# design.net
KiCad netlist of a schematic drawn in Altium Designer
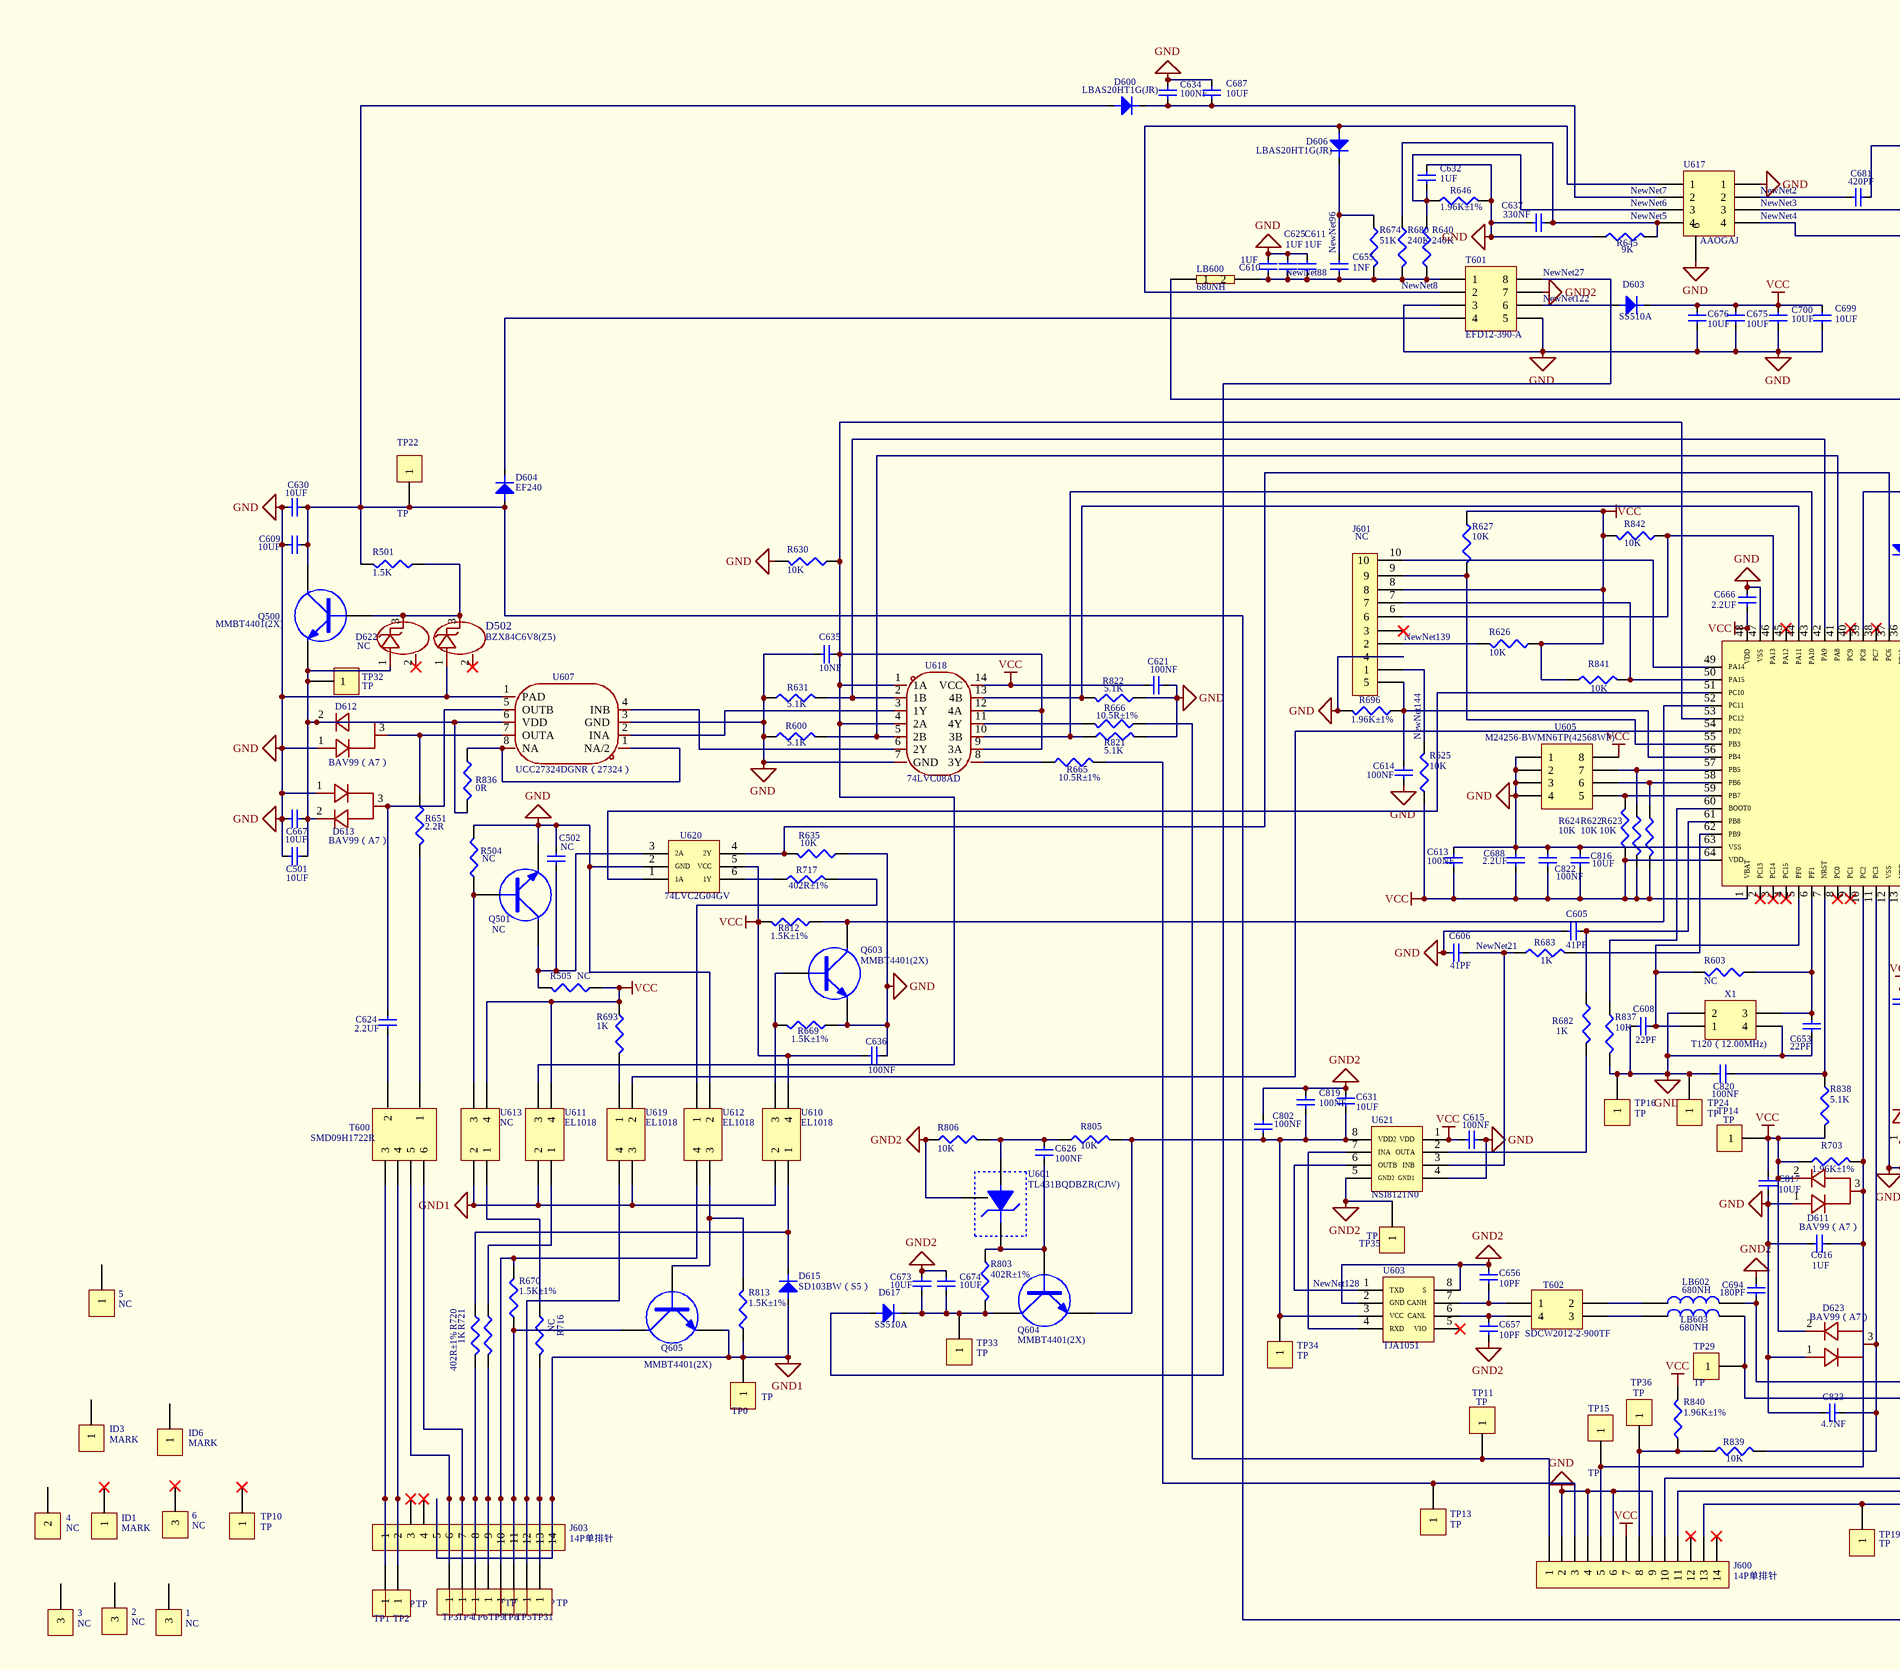
[diagram p0: 小板原理图.SchDoc, left]
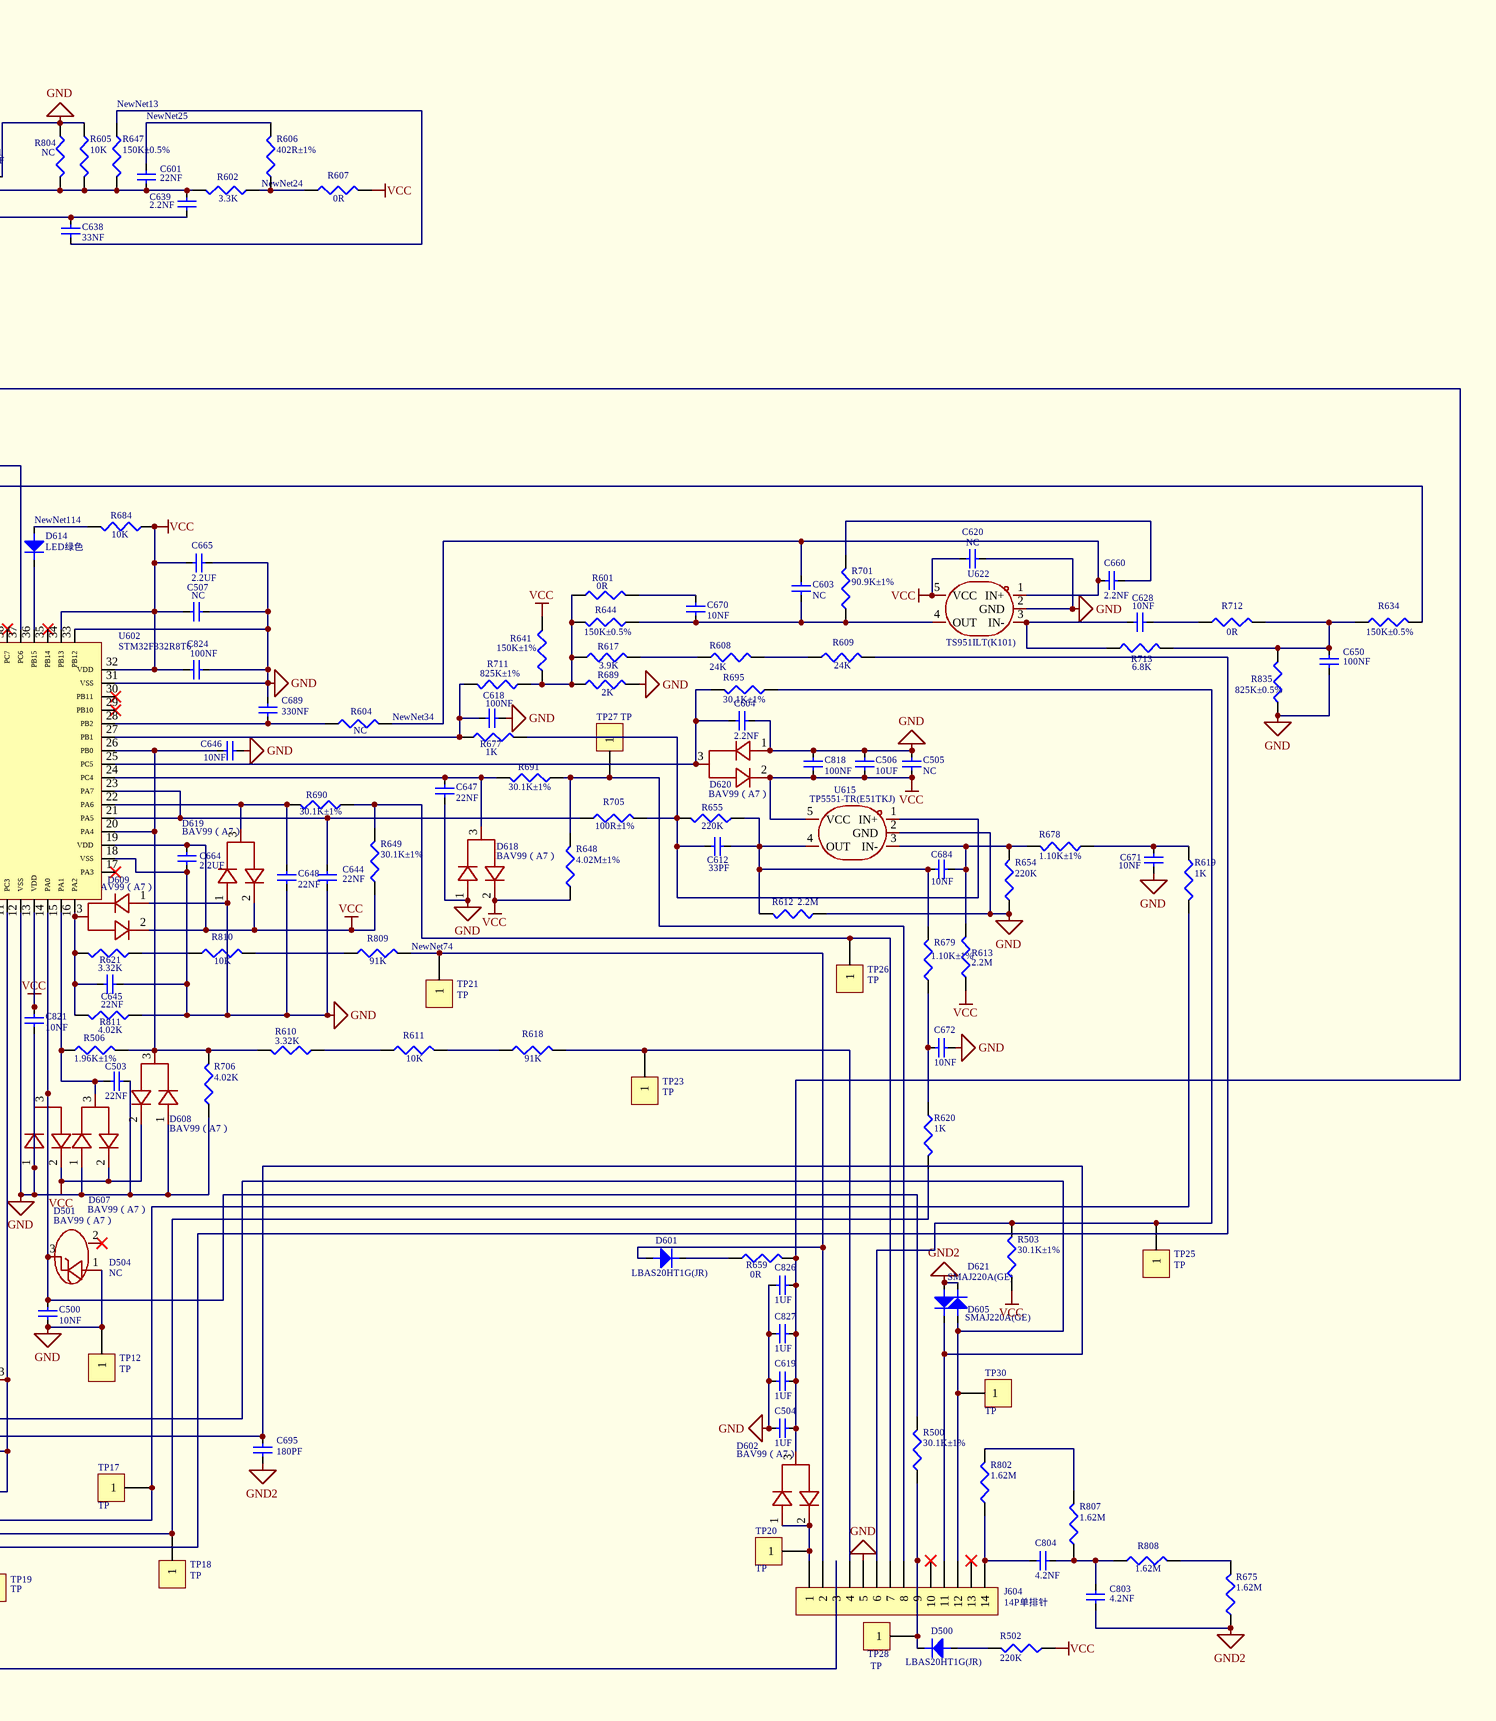
[diagram p1: 小板原理图.SchDoc, right]

(export (version "E")
  (design (tool "Eeschema 10.0.6"))
  (components
    (comp (ref "1") (value "NC") (footprint "27") (libsource (lib "*") (part "NC_")))
    (comp (ref "2") (value "NC") (footprint "28") (libsource (lib "*") (part "NC_")))
    (comp (ref "3") (value "NC") (footprint "29") (libsource (lib "*") (part "NC_")))
    (comp (ref "4") (value "NC") (footprint "30") (libsource (lib "") (part "NC__5")))
    (comp (ref "5") (value "NC") (footprint "30") (libsource (lib "") (part "NC__7")))
    (comp (ref "6") (value "NC") (footprint "30") (libsource (lib "*") (part "NC_")))
    (comp (ref "C500")
      (value "10NF")
      (footprint "33")
      (description "Capacitor")
      (libsource (lib "*") (part "CAP"))
    )
    (comp (ref "C501")
      (value "10UF")
      (footprint "4")
      (description "Capacitor")
      (libsource (lib "*") (part "CAP"))
    )
    (comp (ref "C502")
      (value "NC")
      (footprint "33")
      (description "Capacitor")
      (libsource (lib "*") (part "CAP"))
    )
    (comp (ref "C503")
      (value "22NF")
      (footprint "33")
      (description "Capacitor")
      (libsource (lib "*") (part "CAP"))
    )
    (comp (ref "C504")
      (value "1UF")
      (footprint "3")
      (description "Capacitor")
      (libsource (lib "*") (part "CAP"))
    )
    (comp (ref "C505")
      (value "NC")
      (footprint "3")
      (description "Capacitor")
      (libsource (lib "*") (part "CAP"))
    )
    (comp (ref "C506")
      (value "10UF")
      (footprint "3")
      (description "Capacitor")
      (libsource (lib "*") (part "CAP"))
    )
    (comp (ref "C507")
      (value "NC")
      (footprint "3")
      (description "Capacitor")
      (libsource (lib "*") (part "CAP"))
    )
    (comp (ref "C601")
      (value "22NF")
      (footprint "33")
      (description "Capacitor")
      (libsource (lib "*") (part "CAP"))
    )
    (comp (ref "C603")
      (value "NC")
      (footprint "33")
      (description "Capacitor")
      (libsource (lib "*") (part "CAP"))
    )
    (comp (ref "C604")
      (value "2.2NF")
      (footprint "33")
      (description "Capacitor")
      (libsource (lib "*") (part "CAP"))
    )
    (comp (ref "C605")
      (value "41PF")
      (footprint "33")
      (description "Capacitor")
      (libsource (lib "*") (part "CAP"))
    )
    (comp (ref "C606")
      (value "41PF")
      (footprint "33")
      (description "Capacitor")
      (libsource (lib "*") (part "CAP"))
    )
    (comp (ref "C608")
      (value "22PF")
      (footprint "14")
      (description "Capacitor")
      (libsource (lib "*") (part "CAP"))
    )
    (comp (ref "C609")
      (value "10UF")
      (footprint "4")
      (description "Capacitor")
      (libsource (lib "*") (part "CAP"))
    )
    (comp (ref "C610")
      (value "1UF")
      (footprint "3")
      (description "Capacitor")
      (libsource (lib "*") (part "CAP"))
    )
    (comp (ref "C611")
      (value "1UF")
      (footprint "3")
      (description "Capacitor")
      (libsource (lib "*") (part "CAP"))
    )
    (comp (ref "C612")
      (value "33PF")
      (footprint "33")
      (description "Capacitor")
      (libsource (lib "*") (part "CAP"))
    )
    (comp (ref "C613")
      (value "100NF")
      (footprint "14")
      (description "Capacitor")
      (libsource (lib "*") (part "CAP"))
    )
    (comp (ref "C614")
      (value "100NF")
      (footprint "14")
      (description "Capacitor")
      (libsource (lib "*") (part "CAP"))
    )
    (comp (ref "C615")
      (value "100NF")
      (footprint "14")
      (description "Capacitor")
      (libsource (lib "*") (part "CAP"))
    )
    (comp (ref "C616")
      (value "1UF")
      (footprint "33")
      (description "Capacitor")
      (libsource (lib "*") (part "CAP"))
    )
    (comp (ref "C618")
      (value "100NF")
      (footprint "14")
      (description "Capacitor")
      (libsource (lib "*") (part "CAP"))
    )
    (comp (ref "C619")
      (value "1UF")
      (footprint "32")
      (description "Capacitor")
      (libsource (lib "*") (part "CAP"))
    )
    (comp (ref "C620")
      (value "NC")
      (footprint "14")
      (description "Capacitor")
      (libsource (lib "*") (part "CAP"))
    )
    (comp (ref "C621")
      (value "100NF")
      (footprint "14")
      (description "Capacitor")
      (libsource (lib "*") (part "CAP"))
    )
    (comp (ref "C624")
      (value "2.2UF")
      (footprint "3")
      (description "Capacitor")
      (libsource (lib "*") (part "CAP"))
    )
    (comp (ref "C625")
      (value "1UF")
      (footprint "3")
      (description "Capacitor")
      (libsource (lib "*") (part "CAP"))
    )
    (comp (ref "C626")
      (value "100NF")
      (footprint "14")
      (description "Capacitor")
      (libsource (lib "*") (part "CAP"))
    )
    (comp (ref "C628")
      (value "10NF")
      (footprint "33")
      (description "Capacitor")
      (libsource (lib "*") (part "CAP"))
    )
    (comp (ref "C630")
      (value "10UF")
      (footprint "4")
      (description "Capacitor")
      (libsource (lib "*") (part "CAP"))
    )
    (comp (ref "C631")
      (value "10UF")
      (footprint "4")
      (description "Capacitor")
      (libsource (lib "*") (part "CAP"))
    )
    (comp (ref "C632")
      (value "1UF")
      (footprint "32")
      (description "Capacitor")
      (libsource (lib "*") (part "CAP"))
    )
    (comp (ref "C634")
      (value "100NF")
      (footprint "33")
      (description "Capacitor")
      (libsource (lib "*") (part "CAP"))
    )
    (comp (ref "C635")
      (value "10NF")
      (footprint "33")
      (description "Capacitor")
      (libsource (lib "*") (part "CAP"))
    )
    (comp (ref "C636")
      (value "100NF")
      (footprint "14")
      (description "Capacitor")
      (libsource (lib "*") (part "CAP"))
    )
    (comp (ref "C637")
      (value "330NF")
      (footprint "32")
      (description "Capacitor")
      (libsource (lib "*") (part "CAP"))
    )
    (comp (ref "C638")
      (value "33NF")
      (footprint "14")
      (description "Capacitor")
      (libsource (lib "*") (part "CAP"))
    )
    (comp (ref "C639")
      (value "2.2NF")
      (footprint "33")
      (description "Capacitor")
      (libsource (lib "*") (part "CAP"))
    )
    (comp (ref "C644")
      (value "22NF")
      (footprint "33")
      (description "Capacitor")
      (libsource (lib "*") (part "CAP"))
    )
    (comp (ref "C645")
      (value "22NF")
      (footprint "33")
      (description "Capacitor")
      (libsource (lib "*") (part "CAP"))
    )
    (comp (ref "C646")
      (value "10NF")
      (footprint "33")
      (description "Capacitor")
      (libsource (lib "*") (part "CAP"))
    )
    (comp (ref "C647")
      (value "22NF")
      (footprint "33")
      (description "Capacitor")
      (libsource (lib "*") (part "CAP"))
    )
    (comp (ref "C648")
      (value "22NF")
      (footprint "33")
      (description "Capacitor")
      (libsource (lib "*") (part "CAP"))
    )
    (comp (ref "C650")
      (value "100NF")
      (footprint "33")
      (description "Capacitor")
      (libsource (lib "*") (part "CAP"))
    )
    (comp (ref "C653")
      (value "22PF")
      (footprint "14")
      (description "Capacitor")
      (libsource (lib "*") (part "CAP"))
    )
    (comp (ref "C655")
      (value "1NF")
      (footprint "4")
      (description "Capacitor")
      (libsource (lib "*") (part "CAP"))
    )
    (comp (ref "C656")
      (value "10PF")
      (footprint "33")
      (description "Capacitor")
      (libsource (lib "*") (part "CAP"))
    )
    (comp (ref "C657")
      (value "10PF")
      (footprint "33")
      (description "Capacitor")
      (libsource (lib "*") (part "CAP"))
    )
    (comp (ref "C660")
      (value "2.2NF")
      (footprint "33")
      (description "Capacitor")
      (libsource (lib "*") (part "CAP"))
    )
    (comp (ref "C664")
      (value "2.2UF")
      (footprint "32")
      (description "Capacitor")
      (libsource (lib "*") (part "CAP"))
    )
    (comp (ref "C665")
      (value "2.2UF")
      (footprint "32")
      (description "Capacitor")
      (libsource (lib "*") (part "CAP"))
    )
    (comp (ref "C666")
      (value "2.2UF")
      (footprint "32")
      (description "Capacitor")
      (libsource (lib "*") (part "CAP"))
    )
    (comp (ref "C667")
      (value "10UF")
      (footprint "4")
      (description "Capacitor")
      (libsource (lib "*") (part "CAP"))
    )
    (comp (ref "C670")
      (value "10NF")
      (footprint "33")
      (description "Capacitor")
      (libsource (lib "*") (part "CAP"))
    )
    (comp (ref "C671")
      (value "10NF")
      (footprint "33")
      (description "Capacitor")
      (libsource (lib "*") (part "CAP"))
    )
    (comp (ref "C672")
      (value "10NF")
      (footprint "33")
      (description "Capacitor")
      (libsource (lib "*") (part "CAP"))
    )
    (comp (ref "C673")
      (value "10UF")
      (footprint "4")
      (description "Capacitor")
      (libsource (lib "*") (part "CAP"))
    )
    (comp (ref "C674")
      (value "10UF")
      (footprint "4")
      (description "Capacitor")
      (libsource (lib "*") (part "CAP"))
    )
    (comp (ref "C675")
      (value "10UF")
      (footprint "32")
      (description "Capacitor")
      (libsource (lib "*") (part "CAP"))
    )
    (comp (ref "C676")
      (value "10UF")
      (footprint "32")
      (description "Capacitor")
      (libsource (lib "*") (part "CAP"))
    )
    (comp (ref "C681")
      (value "420PF")
      (footprint "33")
      (description "Capacitor")
      (libsource (lib "*") (part "CAP"))
    )
    (comp (ref "C684")
      (value "10NF")
      (footprint "33")
      (description "Capacitor")
      (libsource (lib "*") (part "CAP"))
    )
    (comp (ref "C687")
      (value "10UF")
      (footprint "4")
      (description "Capacitor")
      (libsource (lib "*") (part "CAP"))
    )
    (comp (ref "C688")
      (value "2.2UF")
      (footprint "32")
      (description "Capacitor")
      (libsource (lib "*") (part "CAP"))
    )
    (comp (ref "C689")
      (value "330NF")
      (footprint "32")
      (description "Capacitor")
      (libsource (lib "*") (part "CAP"))
    )
    (comp (ref "C694")
      (value "180PF")
      (footprint "33")
      (description "Capacitor")
      (libsource (lib "*") (part "CAP"))
    )
    (comp (ref "C695")
      (value "180PF")
      (footprint "33")
      (description "Capacitor")
      (libsource (lib "*") (part "CAP"))
    )
    (comp (ref "C699")
      (value "10UF")
      (footprint "32")
      (description "Capacitor")
      (libsource (lib "*") (part "CAP"))
    )
    (comp (ref "C700")
      (value "10UF")
      (footprint "32")
      (description "Capacitor")
      (libsource (lib "*") (part "CAP"))
    )
    (comp (ref "C802")
      (value "100NF")
      (footprint "14")
      (description "Capacitor")
      (libsource (lib "*") (part "CAP"))
    )
    (comp (ref "C803")
      (value "4.2NF")
      (footprint "4")
      (description "Capacitor")
      (libsource (lib "*") (part "CAP"))
    )
    (comp (ref "C804")
      (value "4.2NF")
      (footprint "4")
      (description "Capacitor")
      (libsource (lib "*") (part "CAP"))
    )
    (comp (ref "C816")
      (value "10UF")
      (footprint "32")
      (description "Capacitor")
      (libsource (lib "*") (part "CAP"))
    )
    (comp (ref "C817")
      (value "10UF")
      (footprint "32")
      (description "Capacitor")
      (libsource (lib "*") (part "CAP"))
    )
    (comp (ref "C818")
      (value "100NF")
      (footprint "14")
      (description "Capacitor")
      (libsource (lib "*") (part "CAP"))
    )
    (comp (ref "C819")
      (value "100NF")
      (footprint "14")
      (description "Capacitor")
      (libsource (lib "*") (part "CAP"))
    )
    (comp (ref "C820")
      (value "100NF")
      (footprint "33")
      (description "Capacitor")
      (libsource (lib "*") (part "CAP"))
    )
    (comp (ref "C821")
      (value "10NF")
      (footprint "33")
      (description "Capacitor")
      (libsource (lib "*") (part "CAP"))
    )
    (comp (ref "C822")
      (value "100NF")
      (footprint "14")
      (description "Capacitor")
      (libsource (lib "*") (part "CAP"))
    )
    (comp (ref "C823")
      (value "4.7NF")
      (footprint "33")
      (description "Capacitor")
      (libsource (lib "*") (part "CAP"))
    )
    (comp (ref "C824")
      (value "100NF")
      (footprint "14")
      (description "Capacitor")
      (libsource (lib "*") (part "CAP"))
    )
    (comp (ref "C826")
      (value "1UF")
      (footprint "32")
      (description "Capacitor")
      (libsource (lib "*") (part "CAP"))
    )
    (comp (ref "C827")
      (value "1UF")
      (footprint "32")
      (description "Capacitor")
      (libsource (lib "*") (part "CAP"))
    )
    (comp (ref "D500")
      (value "LBAS20HT1G(JR)")
      (footprint "18")
      (description "Diode")
      (libsource (lib "*") (part "DIODE_SMD"))
    )
    (comp (ref "D501")
      (value "BAV99（A7）")
      (footprint "31")
      (libsource (lib "altium-import") (part "root_3_BAV99_C7420336_"))
    )
    (comp (ref "D502") (value "BZX84C6V8(Z5)") (footprint "31") (libsource (lib "SCH") (part "BZX84-C6V2")))
    (comp (ref "D504") (value "NC") (footprint "31") (libsource (lib "SCH") (part "BZX84-C6V2")))
    (comp (ref "D600")
      (value "LBAS20HT1G(JR)")
      (footprint "18")
      (description "Diode")
      (libsource (lib "*") (part "DIODE_SMD"))
    )
    (comp (ref "D601")
      (value "LBAS20HT1G(JR)")
      (footprint "18")
      (description "Diode")
      (libsource (lib "*") (part "DIODE_SMD"))
    )
    (comp (ref "D602")
      (value "BAV99（A7）")
      (footprint "31")
      (libsource (lib "altium-import") (part "root_3_BAV99_C7420336_"))
    )
    (comp (ref "D603")
      (value "SS510A")
      (footprint "16")
      (description "Diode")
      (libsource (lib "*") (part "DIODE_SMD"))
    )
    (comp (ref "D604")
      (value "EF240")
      (footprint "17")
      (description "Diode")
      (libsource (lib "*") (part "DIODE_SMD"))
    )
    (comp (ref "D605")
      (value "SMAJ220A(GE)")
      (footprint "19")
      (description "Diode")
      (libsource (lib "*") (part "DIODE_SMD"))
    )
    (comp (ref "D606")
      (value "LBAS20HT1G(JR)")
      (footprint "18")
      (description "Diode")
      (libsource (lib "*") (part "DIODE_SMD"))
    )
    (comp (ref "D607")
      (value "BAV99（A7）")
      (footprint "31")
      (libsource (lib "altium-import") (part "root_3_BAV99_C7420336_"))
    )
    (comp (ref "D608")
      (value "BAV99（A7）")
      (footprint "31")
      (libsource (lib "altium-import") (part "root_3_mirrored_BAV99_C7420336_"))
    )
    (comp (ref "D609")
      (value "BAV99（A7）")
      (footprint "31")
      (libsource (lib "altium-import") (part "root_2_mirrored_BAV99_C7420336_"))
    )
    (comp (ref "D611")
      (value "BAV99（A7）")
      (footprint "31")
      (libsource (lib "altium-import") (part "root_0_mirrored_BAV99_C7420336_"))
    )
    (comp (ref "D612")
      (value "BAV99（A7）")
      (footprint "31")
      (libsource (lib "altium-import") (part "root_0_mirrored_BAV99_C7420336_"))
    )
    (comp (ref "D613")
      (value "BAV99（A7）")
      (footprint "31")
      (libsource (lib "altium-import") (part "root_2_BAV99_C7420336_"))
    )
    (comp (ref "D614")
      (value "LED绿色")
      (footprint "10")
      (description "Diode")
      (libsource (lib "*") (part "DIODE_SMD"))
    )
    (comp (ref "D615")
      (value "SD103BW（S5）")
      (footprint "18")
      (description "Diode")
      (libsource (lib "*") (part "DIODE_SMD"))
    )
    (comp (ref "D617")
      (value "SS510A")
      (footprint "16")
      (description "Diode")
      (libsource (lib "*") (part "DIODE_SMD"))
    )
    (comp (ref "D618")
      (value "BAV99（A7）")
      (footprint "31")
      (libsource (lib "altium-import") (part "root_3_BAV99_C7420336_"))
    )
    (comp (ref "D619")
      (value "BAV99（A7）")
      (footprint "31")
      (libsource (lib "altium-import") (part "root_3_BAV99_C7420336_"))
    )
    (comp (ref "D620")
      (value "BAV99（A7）")
      (footprint "31")
      (libsource (lib "altium-import") (part "root_2_mirrored_BAV99_C7420336_"))
    )
    (comp (ref "D621")
      (value "SMAJ220A(GE)")
      (footprint "19")
      (description "Diode")
      (libsource (lib "*") (part "DIODE_SMD"))
    )
    (comp (ref "D622") (value "NC") (footprint "31") (libsource (lib "SCH") (part "BZX84-C6V2")))
    (comp (ref "D623")
      (value "BAV99（A7）")
      (footprint "31")
      (libsource (lib "altium-import") (part "root_0_mirrored_BAV99_C7420336_"))
    )
    (comp (ref "ID1") (value "MARK") (footprint "30") (libsource (lib "*") (part "MARK_")))
    (comp (ref "ID3") (value "MARK") (footprint "30") (libsource (lib "*") (part "MARK_")))
    (comp (ref "ID6") (value "MARK") (footprint "30") (libsource (lib "*") (part "MARK_")))
    (comp (ref "J600") (value "14P单排针") (footprint "21") (libsource (lib "*") (part "14P单排针 _")))
    (comp (ref "J601") (value "NC") (footprint "25") (libsource (lib "") (part "NC__4")))
    (comp (ref "J603") (value "14P单排针") (footprint "21") (libsource (lib "*") (part "14P单排针 _")))
    (comp (ref "J604") (value "14P单排针") (footprint "21") (libsource (lib "*") (part "14P单排针 _")))
    (comp (ref "LB600") (value "680NH") (footprint "3") (libsource (lib "*") (part "680NH_")))
    (comp (ref "LB602") (value "680NH") (footprint "32") (libsource (lib "*") (part "INDUCTOR1")))
    (comp (ref "LB603") (value "680NH") (footprint "32") (libsource (lib "*") (part "INDUCTOR1")))
    (comp (ref "Q500") (value "MMBT4401(2X)") (footprint "31") (libsource (lib "*") (part "NPN")))
    (comp (ref "Q501") (value "NC") (footprint "31") (libsource (lib "*") (part "NPN")))
    (comp (ref "Q603") (value "MMBT4401(2X)") (footprint "31") (libsource (lib "*") (part "NPN")))
    (comp (ref "Q604") (value "MMBT4401(2X)") (footprint "31") (libsource (lib "*") (part "NPN")))
    (comp (ref "Q605") (value "MMBT4401(2X)") (footprint "31") (libsource (lib "*") (part "NPN")))
    (comp (ref "R500") (value "30.1K±1%") (footprint "33") (libsource (lib "*") (part "RES1")))
    (comp (ref "R501") (value "1.5K") (footprint "32") (libsource (lib "*") (part "RES1")))
    (comp (ref "R502") (value "220K") (footprint "33") (libsource (lib "*") (part "RES1")))
    (comp (ref "R503") (value "30.1K±1%") (footprint "33") (libsource (lib "*") (part "RES1")))
    (comp (ref "R504") (value "NC") (footprint "33") (libsource (lib "*") (part "RES1")))
    (comp (ref "R505") (value "NC") (footprint "33") (libsource (lib "*") (part "RES1")))
    (comp (ref "R506") (value "1.96K±1%") (footprint "33") (libsource (lib "*") (part "RES1")))
    (comp (ref "R600") (value "5.1K") (footprint "33") (libsource (lib "*") (part "RES1")))
    (comp (ref "R601") (value "0R") (footprint "33") (libsource (lib "*") (part "RES1")))
    (comp (ref "R602") (value "3.3K") (footprint "33") (libsource (lib "*") (part "RES1")))
    (comp (ref "R603") (value "NC") (footprint "32") (libsource (lib "*") (part "RES1")))
    (comp (ref "R604") (value "NC") (footprint "33") (libsource (lib "*") (part "RES1")))
    (comp (ref "R605") (value "10K") (footprint "33") (libsource (lib "*") (part "RES1")))
    (comp (ref "R606") (value "402R±1%") (footprint "33") (libsource (lib "*") (part "RES1")))
    (comp (ref "R607") (value "0R") (footprint "33") (libsource (lib "*") (part "RES1")))
    (comp (ref "R608") (value "24K") (footprint "32") (libsource (lib "*") (part "RES1")))
    (comp (ref "R609") (value "24K") (footprint "32") (libsource (lib "*") (part "RES1")))
    (comp (ref "R610") (value "3.32K") (footprint "32") (libsource (lib "*") (part "RES1")))
    (comp (ref "R611") (value "10K") (footprint "32") (libsource (lib "*") (part "RES1")))
    (comp (ref "R612") (value "2.2M") (footprint "32") (libsource (lib "*") (part "RES1")))
    (comp (ref "R613") (value "2.2M") (footprint "32") (libsource (lib "*") (part "RES1")))
    (comp (ref "R617") (value "3.9K") (footprint "32") (libsource (lib "*") (part "RES1")))
    (comp (ref "R618") (value "91K") (footprint "32") (libsource (lib "*") (part "RES1")))
    (comp (ref "R619") (value "1K") (footprint "33") (libsource (lib "*") (part "RES1")))
    (comp (ref "R620") (value "1K") (footprint "33") (libsource (lib "*") (part "RES1")))
    (comp (ref "R621") (value "3.32K") (footprint "32") (libsource (lib "*") (part "RES1")))
    (comp (ref "R622") (value "10K") (footprint "33") (libsource (lib "*") (part "RES1")))
    (comp (ref "R623") (value "10K") (footprint "33") (libsource (lib "*") (part "RES1")))
    (comp (ref "R624") (value "10K") (footprint "33") (libsource (lib "*") (part "RES1")))
    (comp (ref "R625") (value "10K") (footprint "33") (libsource (lib "*") (part "RES1")))
    (comp (ref "R626") (value "10K") (footprint "33") (libsource (lib "*") (part "RES1")))
    (comp (ref "R627") (value "10K") (footprint "33") (libsource (lib "*") (part "RES1")))
    (comp (ref "R630") (value "10K") (footprint "33") (libsource (lib "*") (part "RES1")))
    (comp (ref "R631") (value "5.1K") (footprint "33") (libsource (lib "*") (part "RES1")))
    (comp (ref "R634") (value "150K±0.5%") (footprint "33") (libsource (lib "*") (part "RES1")))
    (comp (ref "R635") (value "10K") (footprint "33") (libsource (lib "*") (part "RES1")))
    (comp (ref "R640") (value "240K") (footprint "32") (libsource (lib "*") (part "RES1")))
    (comp (ref "R641") (value "150K±1%") (footprint "33") (libsource (lib "*") (part "RES1")))
    (comp (ref "R644") (value "150K±0.5%") (footprint "33") (libsource (lib "*") (part "RES1")))
    (comp (ref "R645") (value "9K") (footprint "33") (libsource (lib "*") (part "RES1")))
    (comp (ref "R646") (value "1.96K±1%") (footprint "33") (libsource (lib "*") (part "RES1")))
    (comp (ref "R647") (value "150K±0.5%") (footprint "33") (libsource (lib "*") (part "RES1")))
    (comp (ref "R648") (value "4.02M±1%") (footprint "33") (libsource (lib "*") (part "RES1")))
    (comp (ref "R649") (value "30.1K±1%") (footprint "33") (libsource (lib "*") (part "RES1")))
    (comp (ref "R651") (value "2.2R") (footprint "4") (libsource (lib "*") (part "RES1")))
    (comp (ref "R654") (value "220K") (footprint "33") (libsource (lib "*") (part "RES1")))
    (comp (ref "R655") (value "220K") (footprint "33") (libsource (lib "*") (part "RES1")))
    (comp (ref "R659") (value "0R") (footprint "4") (libsource (lib "*") (part "RES1")))
    (comp (ref "R665") (value "10.5R±1%") (footprint "33") (libsource (lib "*") (part "RES1")))
    (comp (ref "R666") (value "10.5R±1%") (footprint "33") (libsource (lib "*") (part "RES1")))
    (comp (ref "R669") (value "1.5K±1%") (footprint "33") (libsource (lib "*") (part "RES1")))
    (comp (ref "R670") (value "1.5K±1%") (footprint "33") (libsource (lib "*") (part "RES1")))
    (comp (ref "R674") (value "51K") (footprint "4") (libsource (lib "*") (part "RES1")))
    (comp (ref "R675") (value "1.62M") (footprint "4") (libsource (lib "*") (part "RES1")))
    (comp (ref "R677") (value "1K") (footprint "33") (libsource (lib "*") (part "RES1")))
    (comp (ref "R678") (value "1.10K±1%") (footprint "33") (libsource (lib "*") (part "RES1")))
    (comp (ref "R679") (value "1.10K±1%") (footprint "33") (libsource (lib "*") (part "RES1")))
    (comp (ref "R680") (value "240K") (footprint "32") (libsource (lib "*") (part "RES1")))
    (comp (ref "R682") (value "1K") (footprint "33") (libsource (lib "*") (part "RES1")))
    (comp (ref "R683") (value "1K") (footprint "33") (libsource (lib "*") (part "RES1")))
    (comp (ref "R684") (value "10K") (footprint "33") (libsource (lib "*") (part "RES1")))
    (comp (ref "R689") (value "2K") (footprint "32") (libsource (lib "*") (part "RES1")))
    (comp (ref "R690") (value "30.1K±1%") (footprint "33") (libsource (lib "*") (part "RES1")))
    (comp (ref "R691") (value "30.1K±1%") (footprint "33") (libsource (lib "*") (part "RES1")))
    (comp (ref "R693") (value "1K") (footprint "33") (libsource (lib "*") (part "RES1")))
    (comp (ref "R695") (value "30.1K±1%") (footprint "33") (libsource (lib "*") (part "RES1")))
    (comp (ref "R696") (value "1.96K±1%") (footprint "33") (libsource (lib "*") (part "RES1")))
    (comp (ref "R701") (value "90.9K±1%") (footprint "33") (libsource (lib "*") (part "RES1")))
    (comp (ref "R703") (value "1.96K±1%") (footprint "33") (libsource (lib "*") (part "RES1")))
    (comp (ref "R705") (value "100R±1%") (footprint "33") (libsource (lib "*") (part "RES1")))
    (comp (ref "R706") (value "4.02K") (footprint "32") (libsource (lib "*") (part "RES1")))
    (comp (ref "R711") (value "825K±1%") (footprint "33") (libsource (lib "*") (part "RES1")))
    (comp (ref "R712") (value "0R") (footprint "33") (libsource (lib "*") (part "RES1")))
    (comp (ref "R713") (value "6.8K") (footprint "33") (libsource (lib "*") (part "RES1")))
    (comp (ref "R716") (value "NC") (footprint "33") (libsource (lib "*") (part "RES1")))
    (comp (ref "R717") (value "402R±1%") (footprint "33") (libsource (lib "*") (part "RES1")))
    (comp (ref "R720") (value "402R±1%") (footprint "33") (libsource (lib "*") (part "RES1")))
    (comp (ref "R721") (value "1K") (footprint "33") (libsource (lib "*") (part "RES1")))
    (comp (ref "R802") (value "1.62M") (footprint "4") (libsource (lib "*") (part "RES1")))
    (comp (ref "R803") (value "402R±1%") (footprint "33") (libsource (lib "*") (part "RES1")))
    (comp (ref "R804") (value "NC") (footprint "33") (libsource (lib "*") (part "RES1")))
    (comp (ref "R805") (value "10K") (footprint "33") (libsource (lib "*") (part "RES1")))
    (comp (ref "R806") (value "10K") (footprint "33") (libsource (lib "*") (part "RES1")))
    (comp (ref "R807") (value "1.62M") (footprint "4") (libsource (lib "*") (part "RES1")))
    (comp (ref "R808") (value "1.62M") (footprint "4") (libsource (lib "*") (part "RES1")))
    (comp (ref "R809") (value "91K") (footprint "32") (libsource (lib "*") (part "RES1")))
    (comp (ref "R810") (value "10K") (footprint "32") (libsource (lib "*") (part "RES1")))
    (comp (ref "R811") (value "4.02K") (footprint "32") (libsource (lib "*") (part "RES1")))
    (comp (ref "R812") (value "1.5K±1%") (footprint "33") (libsource (lib "*") (part "RES1")))
    (comp (ref "R813") (value "1.5K±1%") (footprint "33") (libsource (lib "*") (part "RES1")))
    (comp (ref "R821") (value "5.1K") (footprint "33") (libsource (lib "*") (part "RES1")))
    (comp (ref "R822") (value "5.1K") (footprint "33") (libsource (lib "*") (part "RES1")))
    (comp (ref "R835") (value "825K±0.5%") (footprint "33") (libsource (lib "*") (part "RES1")))
    (comp (ref "R836") (value "0R") (footprint "33") (libsource (lib "*") (part "RES1")))
    (comp (ref "R837") (value "10K") (footprint "33") (libsource (lib "*") (part "RES1")))
    (comp (ref "R838") (value "5.1K") (footprint "33") (libsource (lib "*") (part "RES1")))
    (comp (ref "R839") (value "10K") (footprint "33") (libsource (lib "*") (part "RES1")))
    (comp (ref "R840") (value "1.96K±1%") (footprint "33") (libsource (lib "*") (part "RES1")))
    (comp (ref "R841") (value "10K") (footprint "33") (libsource (lib "*") (part "RES1")))
    (comp (ref "R842") (value "10K") (footprint "33") (libsource (lib "*") (part "RES1")))
    (comp (ref "T600") (value "SMD09H1722R") (footprint "2") (libsource (lib "*") (part "SMD09H1722R_")))
    (comp (ref "T601") (value "EFD12-390-A") (footprint "20") (libsource (lib "*") (part "EFD12-390-A_")))
    (comp (ref "T602")
      (value "SDCW2012-2-900TF")
      (footprint "24")
      (libsource (lib "*") (part "SDCW2012-2-900TF_"))
    )
    (comp (ref "TP0") (value "TP") (footprint "35") (libsource (lib "*") (part "TP_")))
    (comp (ref "TP1") (value "TP") (footprint "35") (libsource (lib "*") (part "TP_")))
    (comp (ref "TP2") (value "TP") (footprint "35") (libsource (lib "*") (part "TP_")))
    (comp (ref "TP3") (value "TP") (footprint "35") (libsource (lib "*") (part "TP_")))
    (comp (ref "TP4") (value "TP") (footprint "35") (libsource (lib "*") (part "TP_")))
    (comp (ref "TP5") (value "TP") (footprint "35") (libsource (lib "*") (part "TP_")))
    (comp (ref "TP6") (value "TP") (footprint "35") (libsource (lib "*") (part "TP_")))
    (comp (ref "TP7") (value "TP") (footprint "35") (libsource (lib "*") (part "TP_")))
    (comp (ref "TP8") (value "TP") (footprint "35") (libsource (lib "*") (part "TP_")))
    (comp (ref "TP9") (value "TP") (footprint "35") (libsource (lib "*") (part "TP_")))
    (comp (ref "TP10") (value "TP") (footprint "35") (libsource (lib "*") (part "TP_")))
    (comp (ref "TP11") (value "TP") (footprint "35") (libsource (lib "") (part "TP__2")))
    (comp (ref "TP12") (value "TP") (footprint "35") (libsource (lib "*") (part "TP_")))
    (comp (ref "TP13") (value "TP") (footprint "35") (libsource (lib "*") (part "TP_")))
    (comp (ref "TP14") (value "TP") (footprint "35") (libsource (lib "") (part "TP__1")))
    (comp (ref "TP15") (value "TP") (footprint "35") (libsource (lib "") (part "TP__2")))
    (comp (ref "TP16") (value "TP") (footprint "35") (libsource (lib "*") (part "TP_")))
    (comp (ref "TP17") (value "TP") (footprint "35") (libsource (lib "") (part "TP__1")))
    (comp (ref "TP18") (value "TP") (footprint "35") (libsource (lib "*") (part "TP_")))
    (comp (ref "TP19") (value "TP") (footprint "35") (libsource (lib "*") (part "TP_")))
    (comp (ref "TP20") (value "TP") (footprint "35") (libsource (lib "") (part "TP__1")))
    (comp (ref "TP21") (value "TP") (footprint "35") (libsource (lib "*") (part "TP_")))
    (comp (ref "TP22") (value "TP") (footprint "35") (libsource (lib "") (part "TP__2")))
    (comp (ref "TP23") (value "TP") (footprint "35") (libsource (lib "*") (part "TP_")))
    (comp (ref "TP24") (value "TP") (footprint "35") (libsource (lib "*") (part "TP_")))
    (comp (ref "TP25") (value "TP") (footprint "35") (libsource (lib "*") (part "TP_")))
    (comp (ref "TP26") (value "TP") (footprint "35") (libsource (lib "*") (part "TP_")))
    (comp (ref "TP27") (value "TP") (footprint "35") (libsource (lib "") (part "TP__2")))
    (comp (ref "TP28") (value "TP") (footprint "35") (libsource (lib "") (part "TP__1")))
    (comp (ref "TP29") (value "TP") (footprint "35") (libsource (lib "") (part "TP__1")))
    (comp (ref "TP30") (value "TP") (footprint "35") (libsource (lib "") (part "TP__3")))
    (comp (ref "TP31") (value "TP") (footprint "35") (libsource (lib "*") (part "TP_")))
    (comp (ref "TP32") (value "TP") (footprint "35") (libsource (lib "") (part "TP__3")))
    (comp (ref "TP33") (value "TP") (footprint "35") (libsource (lib "*") (part "TP_")))
    (comp (ref "TP34") (value "TP") (footprint "35") (libsource (lib "*") (part "TP_")))
    (comp (ref "TP35") (value "TP") (footprint "35") (libsource (lib "*") (part "TP_")))
    (comp (ref "TP36") (value "TP") (footprint "35") (libsource (lib "") (part "TP__2")))
    (comp (ref "U601")
      (value "TL431BQDBZR(CJW)")
      (footprint "31")
      (description "Schottky Diode")
      (libsource (lib "*") (part "TL431AC"))
    )
    (comp (ref "U602")
      (value "STM32F332R8T6")
      (footprint "11")
      (libsource (lib "EN11CTLBI VER.A-1.2MM-OK") (part "NC__1"))
    )
    (comp (ref "U603") (value "TJA1051") (footprint "12") (libsource (lib "") (part "NC__6")))
    (comp (ref "U605")
      (value "M24256-BWMN6TP(42568WP)")
      (footprint "12")
      (libsource (lib "*") (part "M24256-BWMN6TP(42568WP)_"))
    )
    (comp (ref "U607")
      (value "UCC27324DGNR（27324）")
      (footprint "6")
      (libsource (lib "altium-import") (part "root_2_UCC27324DGNR_"))
    )
    (comp (ref "U610") (value "EL1018") (footprint "7") (libsource (lib "") (part "NC__3")))
    (comp (ref "U611") (value "EL1018") (footprint "7") (libsource (lib "") (part "NC__3")))
    (comp (ref "U612") (value "EL1018") (footprint "7") (libsource (lib "") (part "NC__1")))
    (comp (ref "U613") (value "NC") (footprint "7") (libsource (lib "") (part "NC__3")))
    (comp (ref "U615")
      (value "TP5551-TR(E51TKJ)")
      (footprint "15")
      (libsource (lib "SCH") (part "RY3421-sot23-6"))
    )
    (comp (ref "U617") (value "AAOGAJ") (footprint "23") (libsource (lib "*") (part "AAOGAJ_")))
    (comp (ref "U618")
      (value "74LVC08AD")
      (footprint "9")
      (libsource (lib "altium-import") (part "root_0_SN74LVC08ADR_"))
    )
    (comp (ref "U619") (value "EL1018") (footprint "7") (libsource (lib "") (part "NC__1")))
    (comp (ref "U620") (value "74LVC2G04GV") (footprint "26") (libsource (lib "") (part "NC__8")))
    (comp (ref "U621") (value "NSI8121N0") (footprint "12") (libsource (lib "") (part "NC__2")))
    (comp (ref "U622")
      (value "TS951ILT(K101)")
      (footprint "15")
      (libsource (lib "SCH") (part "RY3421-sot23-6"))
    )
    (comp (ref "X1") (value "T120（12.00MHz)") (footprint "13") (libsource (lib "*") (part "T120（12.00MHz)_")))
  )
  (nets
    (net (code "1") (name "/NewNet2") (class "Default")
      (node (ref "C681") (pin "1") (pinfunction "1_1") (pintype "passive"))
      (node (ref "U617") (pin "2") (pinfunction "2_2") (pintype "passive"))
    )
    (net (code "2") (name "/NewNet3") (class "Default")
      (node (ref "C601") (pin "2") (pinfunction "2_2") (pintype "passive"))
      (node (ref "C639") (pin "2") (pinfunction "2_2") (pintype "passive"))
      (node (ref "R602") (pin "2") (pinfunction "2_2") (pintype "passive"))
      (node (ref "R605") (pin "2") (pinfunction "2_2") (pintype "passive"))
      (node (ref "R647") (pin "2") (pinfunction "2_2") (pintype "passive"))
      (node (ref "R804") (pin "2") (pinfunction "2_2") (pintype "passive"))
      (node (ref "U617") (pin "3") (pinfunction "3_3") (pintype "passive"))
    )
    (net (code "3") (name "/NewNet4") (class "Default")
      (node (ref "C638") (pin "2") (pinfunction "2_2") (pintype "passive"))
      (node (ref "C639") (pin "1") (pinfunction "1_1") (pintype "passive"))
      (node (ref "U617") (pin "4") (pinfunction "4_4") (pintype "passive"))
    )
    (net (code "4") (name "/NewNet5") (class "Default")
      (node (ref "C637") (pin "2") (pinfunction "2_2") (pintype "passive"))
      (node (ref "R645") (pin "2") (pinfunction "2_2") (pintype "passive"))
      (node (ref "R680") (pin "1") (pinfunction "1_1") (pintype "passive"))
      (node (ref "U617") (pin "4") (pinfunction "4_4") (pintype "passive"))
    )
    (net (code "5") (name "/NewNet6") (class "Default")
      (node (ref "C632") (pin "2") (pinfunction "2_2") (pintype "passive"))
      (node (ref "R640") (pin "2") (pinfunction "2_2") (pintype "passive"))
      (node (ref "R646") (pin "1") (pinfunction "1_1") (pintype "passive"))
      (node (ref "U617") (pin "3") (pinfunction "3_3") (pintype "passive"))
    )
    (net (code "6") (name "/NewNet7") (class "Default")
      (node (ref "C634") (pin "2") (pinfunction "2_2") (pintype "passive"))
      (node (ref "C687") (pin "2") (pinfunction "2_2") (pintype "passive"))
      (node (ref "D600") (pin "1") (pinfunction "K_1") (pintype "passive"))
      (node (ref "U617") (pin "2") (pinfunction "2_2") (pintype "passive"))
    )
    (net (code "7") (name "/NewNet8") (class "Default")
      (node (ref "D606") (pin "2") (pinfunction "A_2") (pintype "passive"))
      (node (ref "T601") (pin "2") (pinfunction "2_2") (pintype "passive"))
      (node (ref "U617") (pin "1") (pinfunction "1_1") (pintype "passive"))
    )
    (net (code "8") (name "/NewNet13") (class "Default")
      (node (ref "C638") (pin "1") (pinfunction "1_1") (pintype "passive"))
      (node (ref "R647") (pin "1") (pinfunction "1_1") (pintype "passive"))
    )
    (net (code "9") (name "/NewNet21") (class "Default")
      (node (ref "C606") (pin "2") (pinfunction "2_2") (pintype "passive"))
      (node (ref "R683") (pin "1") (pinfunction "1_1") (pintype "passive"))
      (node (ref "U621") (pin "3") (pinfunction "INB_3") (pintype "passive"))
    )
    (net (code "10") (name "/NewNet24") (class "Default")
      (node (ref "R602") (pin "1") (pinfunction "1_1") (pintype "passive"))
      (node (ref "R606") (pin "1") (pinfunction "1_1") (pintype "passive"))
      (node (ref "R607") (pin "1") (pinfunction "1_1") (pintype "passive"))
    )
    (net (code "11") (name "/NewNet25") (class "Default")
      (node (ref "C601") (pin "1") (pinfunction "1_1") (pintype "passive"))
      (node (ref "R606") (pin "2") (pinfunction "2_2") (pintype "passive"))
    )
    (net (code "12") (name "/NewNet27") (class "Default")
      (node (ref "D617") (pin "2") (pinfunction "A_2") (pintype "passive"))
      (node (ref "T601") (pin "8") (pinfunction "8_8") (pintype "passive"))
    )
    (net (code "13") (name "/NewNet34") (class "Default")
      (node (ref "C603") (pin "2") (pinfunction "2_2") (pintype "passive"))
      (node (ref "C660") (pin "2") (pinfunction "2_2") (pintype "passive"))
      (node (ref "R604") (pin "2") (pinfunction "2_2") (pintype "passive"))
      (node (ref "U622") (pin "1") (pinfunction "IN+_1") (pintype "passive"))
    )
    (net (code "14") (name "/NewNet74") (class "Default")
      (node (ref "D601") (pin "2") (pinfunction "A_2") (pintype "passive"))
      (node (ref "J604") (pin "2") (pinfunction "2_2") (pintype "passive"))
      (node (ref "R809") (pin "2") (pinfunction "2_2") (pintype "passive"))
      (node (ref "TP21") (pin "1") (pinfunction "1_1") (pintype "passive"))
    )
    (net (code "15") (name "/NewNet88") (class "Default")
      (node (ref "C610") (pin "2") (pinfunction "2_2") (pintype "passive"))
      (node (ref "C611") (pin "2") (pinfunction "2_2") (pintype "passive"))
      (node (ref "C625") (pin "2") (pinfunction "2_2") (pintype "passive"))
      (node (ref "C655") (pin "2") (pinfunction "2_2") (pintype "passive"))
      (node (ref "LB600") (pin "2") (pinfunction "2_2") (pintype "passive"))
      (node (ref "R640") (pin "1") (pinfunction "1_1") (pintype "passive"))
      (node (ref "R674") (pin "2") (pinfunction "2_2") (pintype "passive"))
      (node (ref "R680") (pin "2") (pinfunction "2_2") (pintype "passive"))
      (node (ref "T601") (pin "1") (pinfunction "1_1") (pintype "passive"))
    )
    (net (code "16") (name "/NewNet96") (class "Default")
      (node (ref "C655") (pin "1") (pinfunction "1_1") (pintype "passive"))
      (node (ref "D606") (pin "1") (pinfunction "K_1") (pintype "passive"))
      (node (ref "R674") (pin "1") (pinfunction "1_1") (pintype "passive"))
    )
    (net (code "17") (name "/NewNet114") (class "Default")
      (node (ref "D614") (pin "2") (pinfunction "A_2") (pintype "passive"))
      (node (ref "R684") (pin "2") (pinfunction "2_2") (pintype "passive"))
    )
    (net (code "18") (name "/NewNet122") (class "Default")
      (node (ref "D603") (pin "2") (pinfunction "A_2") (pintype "passive"))
      (node (ref "T601") (pin "6") (pinfunction "6_6") (pintype "passive"))
    )
    (net (code "19") (name "/NewNet128") (class "Default")
      (node (ref "U603") (pin "1") (pinfunction "TXD_1") (pintype "passive"))
      (node (ref "U621") (pin "6") (pinfunction "OUTB_6") (pintype "passive"))
    )
    (net (code "20") (name "/NewNet139") (class "Default")
      (node (ref "J601") (pin "2") (pinfunction "2_2") (pintype "passive"))
      (node (ref "R626") (pin "2") (pinfunction "2_2") (pintype "passive"))
    )
    (net (code "21") (name "/NewNet144") (class "Default")
      (node (ref "J601") (pin "1") (pinfunction "1_1") (pintype "passive"))
      (node (ref "R625") (pin "2") (pinfunction "2_2") (pintype "passive"))
    )
    (net (code "22") (name "GND") (class "Default")
      (node (ref "C500") (pin "1") (pinfunction "1_1") (pintype "passive"))
      (node (ref "C501") (pin "2") (pinfunction "2_2") (pintype "passive"))
      (node (ref "C502") (pin "2") (pinfunction "2_2") (pintype "passive"))
      (node (ref "C503") (pin "1") (pinfunction "1_1") (pintype "passive"))
      (node (ref "C504") (pin "2") (pinfunction "2_2") (pintype "passive"))
      (node (ref "C505") (pin "2") (pinfunction "2_2") (pintype "passive"))
      (node (ref "C506") (pin "2") (pinfunction "2_2") (pintype "passive"))
      (node (ref "C507") (pin "1") (pinfunction "1_1") (pintype "passive"))
      (node (ref "C604") (pin "1") (pinfunction "1_1") (pintype "passive"))
      (node (ref "C605") (pin "2") (pinfunction "2_2") (pintype "passive"))
      (node (ref "C606") (pin "1") (pinfunction "1_1") (pintype "passive"))
      (node (ref "C608") (pin "1") (pinfunction "1_1") (pintype "passive"))
      (node (ref "C609") (pin "1") (pinfunction "1_1") (pintype "passive"))
      (node (ref "C610") (pin "1") (pinfunction "1_1") (pintype "passive"))
      (node (ref "C611") (pin "1") (pinfunction "1_1") (pintype "passive"))
      (node (ref "C613") (pin "1") (pinfunction "1_1") (pintype "passive"))
      (node (ref "C614") (pin "2") (pinfunction "2_2") (pintype "passive"))
      (node (ref "C615") (pin "2") (pinfunction "2_2") (pintype "passive"))
      (node (ref "C616") (pin "2") (pinfunction "2_2") (pintype "passive"))
      (node (ref "C618") (pin "1") (pinfunction "1_1") (pintype "passive"))
      (node (ref "C619") (pin "1") (pinfunction "1_1") (pintype "passive"))
      (node (ref "C620") (pin "1") (pinfunction "1_1") (pintype "passive"))
      (node (ref "C621") (pin "1") (pinfunction "1_1") (pintype "passive"))
      (node (ref "C625") (pin "1") (pinfunction "1_1") (pintype "passive"))
      (node (ref "C630") (pin "1") (pinfunction "1_1") (pintype "passive"))
      (node (ref "C632") (pin "1") (pinfunction "1_1") (pintype "passive"))
      (node (ref "C634") (pin "1") (pinfunction "1_1") (pintype "passive"))
      (node (ref "C635") (pin "2") (pinfunction "2_2") (pintype "passive"))
      (node (ref "C636") (pin "2") (pinfunction "2_2") (pintype "passive"))
      (node (ref "C637") (pin "1") (pinfunction "1_1") (pintype "passive"))
      (node (ref "C644") (pin "2") (pinfunction "2_2") (pintype "passive"))
      (node (ref "C645") (pin "1") (pinfunction "1_1") (pintype "passive"))
      (node (ref "C646") (pin "1") (pinfunction "1_1") (pintype "passive"))
      (node (ref "C647") (pin "1") (pinfunction "1_1") (pintype "passive"))
      (node (ref "C648") (pin "1") (pinfunction "1_1") (pintype "passive"))
      (node (ref "C650") (pin "2") (pinfunction "2_2") (pintype "passive"))
      (node (ref "C653") (pin "1") (pinfunction "1_1") (pintype "passive"))
      (node (ref "C664") (pin "2") (pinfunction "2_2") (pintype "passive"))
      (node (ref "C665") (pin "1") (pinfunction "1_1") (pintype "passive"))
      (node (ref "C666") (pin "2") (pinfunction "2_2") (pintype "passive"))
      (node (ref "C667") (pin "1") (pinfunction "1_1") (pintype "passive"))
      (node (ref "C671") (pin "2") (pinfunction "2_2") (pintype "passive"))
      (node (ref "C672") (pin "2") (pinfunction "2_2") (pintype "passive"))
      (node (ref "C675") (pin "2") (pinfunction "2_2") (pintype "passive"))
      (node (ref "C676") (pin "2") (pinfunction "2_2") (pintype "passive"))
      (node (ref "C681") (pin "2") (pinfunction "2_2") (pintype "passive"))
      (node (ref "C687") (pin "1") (pinfunction "1_1") (pintype "passive"))
      (node (ref "C688") (pin "1") (pinfunction "1_1") (pintype "passive"))
      (node (ref "C689") (pin "1") (pinfunction "1_1") (pintype "passive"))
      (node (ref "C699") (pin "2") (pinfunction "2_2") (pintype "passive"))
      (node (ref "C700") (pin "2") (pinfunction "2_2") (pintype "passive"))
      (node (ref "C816") (pin "1") (pinfunction "1_1") (pintype "passive"))
      (node (ref "C817") (pin "1") (pinfunction "1_1") (pintype "passive"))
      (node (ref "C818") (pin "1") (pinfunction "1_1") (pintype "passive"))
      (node (ref "C820") (pin "2") (pinfunction "2_2") (pintype "passive"))
      (node (ref "C821") (pin "1") (pinfunction "1_1") (pintype "passive"))
      (node (ref "C822") (pin "2") (pinfunction "2_2") (pintype "passive"))
      (node (ref "C823") (pin "1") (pinfunction "1_1") (pintype "passive"))
      (node (ref "C824") (pin "1") (pinfunction "1_1") (pintype "passive"))
      (node (ref "C826") (pin "1") (pinfunction "1_1") (pintype "passive"))
      (node (ref "C827") (pin "1") (pinfunction "1_1") (pintype "passive"))
      (node (ref "D501") (pin "1") (pinfunction "1_1") (pintype "passive"))
      (node (ref "D502") (pin "1") (pinfunction "A_1") (pintype "passive"))
      (node (ref "D504") (pin "1") (pinfunction "A_1") (pintype "passive"))
      (node (ref "D607") (pin "1") (pinfunction "1_1") (pintype "passive"))
      (node (ref "D608") (pin "1") (pinfunction "1_1") (pintype "passive"))
      (node (ref "D609") (pin "1") (pinfunction "1_1") (pintype "passive"))
      (node (ref "D611") (pin "1") (pinfunction "1_1") (pintype "passive"))
      (node (ref "D612") (pin "1") (pinfunction "1_1") (pintype "passive"))
      (node (ref "D613") (pin "1") (pinfunction "1_1") (pintype "passive"))
      (node (ref "D618") (pin "1") (pinfunction "1_1") (pintype "passive"))
      (node (ref "D619") (pin "1") (pinfunction "1_1") (pintype "passive"))
      (node (ref "D620") (pin "1") (pinfunction "1_1") (pintype "passive"))
      (node (ref "D623") (pin "1") (pinfunction "1_1") (pintype "passive"))
      (node (ref "J600") (pin "2") (pinfunction "2_2") (pintype "passive"))
      (node (ref "J600") (pin "4") (pinfunction "4_4") (pintype "passive"))
      (node (ref "J600") (pin "6") (pinfunction "6_6") (pintype "passive"))
      (node (ref "J600") (pin "9") (pinfunction "9_9") (pintype "passive"))
      (node (ref "J601") (pin "4") (pinfunction "4_4") (pintype "passive"))
      (node (ref "J604") (pin "5") (pinfunction "5_5") (pintype "passive"))
      (node (ref "Q501") (pin "2") (pinfunction "2_2") (pintype "passive"))
      (node (ref "Q603") (pin "2") (pinfunction "2_2") (pintype "passive"))
      (node (ref "R504") (pin "2") (pinfunction "2_2") (pintype "passive"))
      (node (ref "R600") (pin "1") (pinfunction "1_1") (pintype "passive"))
      (node (ref "R605") (pin "1") (pinfunction "1_1") (pintype "passive"))
      (node (ref "R612") (pin "1") (pinfunction "1_1") (pintype "passive"))
      (node (ref "R630") (pin "2") (pinfunction "2_2") (pintype "passive"))
      (node (ref "R631") (pin "1") (pinfunction "1_1") (pintype "passive"))
      (node (ref "R635") (pin "1") (pinfunction "1_1") (pintype "passive"))
      (node (ref "R645") (pin "1") (pinfunction "1_1") (pintype "passive"))
      (node (ref "R646") (pin "2") (pinfunction "2_2") (pintype "passive"))
      (node (ref "R654") (pin "1") (pinfunction "1_1") (pintype "passive"))
      (node (ref "R669") (pin "1") (pinfunction "1_1") (pintype "passive"))
      (node (ref "R689") (pin "2") (pinfunction "2_2") (pintype "passive"))
      (node (ref "R696") (pin "2") (pinfunction "2_2") (pintype "passive"))
      (node (ref "R706") (pin "1") (pinfunction "1_1") (pintype "passive"))
      (node (ref "R804") (pin "1") (pinfunction "1_1") (pintype "passive"))
      (node (ref "R811") (pin "1") (pinfunction "1_1") (pintype "passive"))
      (node (ref "R821") (pin "2") (pinfunction "2_2") (pintype "passive"))
      (node (ref "R822") (pin "1") (pinfunction "1_1") (pintype "passive"))
      (node (ref "R835") (pin "1") (pinfunction "1_1") (pintype "passive"))
      (node (ref "R837") (pin "2") (pinfunction "2_2") (pintype "passive"))
      (node (ref "T601") (pin "3") (pinfunction "3_3") (pintype "passive"))
      (node (ref "T601") (pin "5") (pinfunction "5_5") (pintype "passive"))
      (node (ref "TP12") (pin "1") (pinfunction "1_1") (pintype "passive"))
      (node (ref "TP16") (pin "1") (pinfunction "1_1") (pintype "passive"))
      (node (ref "TP24") (pin "1") (pinfunction "1_1") (pintype "passive"))
      (node (ref "U602") (pin "12") (pinfunction "VSS_12") (pintype "passive"))
      (node (ref "U602") (pin "18") (pinfunction "VSS_18") (pintype "passive"))
      (node (ref "U602") (pin "31") (pinfunction "VSS_31") (pintype "passive"))
      (node (ref "U602") (pin "33") (pinfunction "PB12_33") (pintype "passive"))
      (node (ref "U602") (pin "47") (pinfunction "VSS_47") (pintype "passive"))
      (node (ref "U602") (pin "63") (pinfunction "VSS_63") (pintype "passive"))
      (node (ref "U605") (pin "1") (pinfunction "1_1") (pintype "passive"))
      (node (ref "U605") (pin "2") (pinfunction "2_2") (pintype "passive"))
      (node (ref "U605") (pin "3") (pinfunction "3_3") (pintype "passive"))
      (node (ref "U605") (pin "4") (pinfunction "4_4") (pintype "passive"))
      (node (ref "U607") (pin "1") (pinfunction "PAD_1") (pintype "passive"))
      (node (ref "U607") (pin "3") (pinfunction "GND_3") (pintype "passive"))
      (node (ref "U612") (pin "2") (pinfunction "2_2") (pintype "passive"))
      (node (ref "U615") (pin "2") (pinfunction "GND_2") (pintype "passive"))
      (node (ref "U617") (pin "1") (pinfunction "1_1") (pintype "passive"))
      (node (ref "U617") (pin "6") (pinfunction "6_6") (pintype "passive"))
      (node (ref "U618") (pin "7") (pinfunction "GND_7") (pintype "passive"))
      (node (ref "U620") (pin "2") (pinfunction "GND_2") (pintype "passive"))
      (node (ref "U621") (pin "4") (pinfunction "GND1_4") (pintype "passive"))
      (node (ref "U622") (pin "2") (pinfunction "GND_2") (pintype "passive"))
      (node (ref "X1") (pin "2") (pinfunction "2_2") (pintype "passive"))
      (node (ref "X1") (pin "4") (pinfunction "4_4") (pintype "passive"))
    )
    (net (code "23") (name "GND1") (class "Default")
      (node (ref "D615") (pin "2") (pinfunction "A_2") (pintype "passive"))
      (node (ref "J603") (pin "14") (pinfunction "14_14") (pintype "passive"))
      (node (ref "J603") (pin "5") (pinfunction "5_5") (pintype "passive"))
      (node (ref "Q605") (pin "2") (pinfunction "2_2") (pintype "passive"))
      (node (ref "R813") (pin "1") (pinfunction "1_1") (pintype "passive"))
      (node (ref "TP0") (pin "1") (pinfunction "1_1") (pintype "passive"))
      (node (ref "U610") (pin "2") (pinfunction "2_2") (pintype "passive"))
      (node (ref "U611") (pin "2") (pinfunction "2_2") (pintype "passive"))
      (node (ref "U613") (pin "2") (pinfunction "2_2") (pintype "passive"))
      (node (ref "U619") (pin "3") (pinfunction "3_3") (pintype "passive"))
    )
    (net (code "24") (name "GND2") (class "Default")
      (node (ref "C631") (pin "2") (pinfunction "2_2") (pintype "passive"))
      (node (ref "C656") (pin "2") (pinfunction "2_2") (pintype "passive"))
      (node (ref "C657") (pin "1") (pinfunction "1_1") (pintype "passive"))
      (node (ref "C673") (pin "1") (pinfunction "1_1") (pintype "passive"))
      (node (ref "C674") (pin "1") (pinfunction "1_1") (pintype "passive"))
      (node (ref "C694") (pin "2") (pinfunction "2_2") (pintype "passive"))
      (node (ref "C695") (pin "2") (pinfunction "2_2") (pintype "passive"))
      (node (ref "C802") (pin "1") (pinfunction "1_1") (pintype "passive"))
      (node (ref "C803") (pin "2") (pinfunction "2_2") (pintype "passive"))
      (node (ref "C819") (pin "1") (pinfunction "1_1") (pintype "passive"))
      (node (ref "D605") (pin "1") (pinfunction "K_1") (pintype "passive"))
      (node (ref "D621") (pin "2") (pinfunction "A_2") (pintype "passive"))
      (node (ref "R675") (pin "1") (pinfunction "1_1") (pintype "passive"))
      (node (ref "R806") (pin "2") (pinfunction "2_2") (pintype "passive"))
      (node (ref "T601") (pin "7") (pinfunction "7_7") (pintype "passive"))
      (node (ref "TP35") (pin "1") (pinfunction "1_1") (pintype "passive"))
      (node (ref "U601") (pin "3") (pinfunction "R_3") (pintype "passive"))
      (node (ref "U603") (pin "2") (pinfunction "GND_2") (pintype "passive"))
      (node (ref "U603") (pin "8") (pinfunction "S_8") (pintype "passive"))
      (node (ref "U621") (pin "5") (pinfunction "GND2_5") (pintype "passive"))
    )
    (net (code "25") (name "Net-(C504-Pad1)") (class "Default")
      (node (ref "C504") (pin "1") (pinfunction "1_1") (pintype "passive"))
      (node (ref "C619") (pin "2") (pinfunction "2_2") (pintype "passive"))
      (node (ref "C826") (pin "2") (pinfunction "2_2") (pintype "passive"))
      (node (ref "C827") (pin "2") (pinfunction "2_2") (pintype "passive"))
      (node (ref "D602") (pin "3") (pinfunction "3_3") (pintype "passive"))
      (node (ref "LB600") (pin "1") (pinfunction "1_1") (pintype "passive"))
      (node (ref "R659") (pin "2") (pinfunction "2_2") (pintype "passive"))
    )
    (net (code "26") (name "Net-(C624-Pad2)") (class "Default")
      (node (ref "C624") (pin "2") (pinfunction "2_2") (pintype "passive"))
      (node (ref "T600") (pin "2") (pinfunction "2_2") (pintype "passive"))
    )
    (net (code "27") (name "Net-(C628-Pad2)") (class "Default")
      (node (ref "C628") (pin "2") (pinfunction "2_2") (pintype "passive"))
      (node (ref "R712") (pin "1") (pinfunction "1_1") (pintype "passive"))
    )
    (net (code "28") (name "Net-(C650-Pad1)") (class "Default")
      (node (ref "C650") (pin "1") (pinfunction "1_1") (pintype "passive"))
      (node (ref "R634") (pin "1") (pinfunction "1_1") (pintype "passive"))
      (node (ref "R712") (pin "2") (pinfunction "2_2") (pintype "passive"))
      (node (ref "R713") (pin "2") (pinfunction "2_2") (pintype "passive"))
      (node (ref "R835") (pin "2") (pinfunction "2_2") (pintype "passive"))
    )
    (net (code "29") (name "Net-(C660-Pad1)") (class "Default")
      (node (ref "C660") (pin "1") (pinfunction "1_1") (pintype "passive"))
      (node (ref "R701") (pin "2") (pinfunction "2_2") (pintype "passive"))
    )
    (net (code "30") (name "Net-(C670-Pad2)") (class "Default")
      (node (ref "C670") (pin "2") (pinfunction "2_2") (pintype "passive"))
      (node (ref "R601") (pin "2") (pinfunction "2_2") (pintype "passive"))
    )
    (net (code "31") (name "Net-(C671-Pad1)") (class "Default")
      (node (ref "C671") (pin "1") (pinfunction "1_1") (pintype "passive"))
      (node (ref "R619") (pin "1") (pinfunction "1_1") (pintype "passive"))
      (node (ref "R678") (pin "1") (pinfunction "1_1") (pintype "passive"))
    )
    (net (code "32") (name "Net-(C672-Pad1)") (class "Default")
      (node (ref "C672") (pin "1") (pinfunction "1_1") (pintype "passive"))
      (node (ref "R620") (pin "1") (pinfunction "1_1") (pintype "passive"))
      (node (ref "R679") (pin "1") (pinfunction "1_1") (pintype "passive"))
    )
    (net (code "33") (name "Net-(C803-Pad1)") (class "Default")
      (node (ref "C803") (pin "1") (pinfunction "1_1") (pintype "passive"))
      (node (ref "C804") (pin "2") (pinfunction "2_2") (pintype "passive"))
      (node (ref "R807") (pin "1") (pinfunction "1_1") (pintype "passive"))
      (node (ref "R808") (pin "1") (pinfunction "1_1") (pintype "passive"))
    )
    (net (code "34") (name "Net-(C804-Pad1)") (class "Default")
      (node (ref "C804") (pin "1") (pinfunction "1_1") (pintype "passive"))
      (node (ref "J604") (pin "14") (pinfunction "14_14") (pintype "passive"))
      (node (ref "R802") (pin "1") (pinfunction "1_1") (pintype "passive"))
    )
    (net (code "35") (name "Net-(D500-A)") (class "Default")
      (node (ref "D500") (pin "2") (pinfunction "A_2") (pintype "passive"))
      (node (ref "R502") (pin "2") (pinfunction "2_2") (pintype "passive"))
    )
    (net (code "36") (name "Net-(D500-K)") (class "Default")
      (node (ref "D500") (pin "1") (pinfunction "K_1") (pintype "passive"))
      (node (ref "J604") (pin "9") (pinfunction "9_9") (pintype "passive"))
      (node (ref "R500") (pin "1") (pinfunction "1_1") (pintype "passive"))
      (node (ref "TP28") (pin "1") (pinfunction "1_1") (pintype "passive"))
    )
    (net (code "37") (name "Net-(D502-K)") (class "Default")
      (node (ref "D502") (pin "3") (pinfunction "K_3") (pintype "passive"))
      (node (ref "D622") (pin "3") (pinfunction "K_3") (pintype "passive"))
      (node (ref "Q500") (pin "1") (pinfunction "1_1") (pintype "passive"))
      (node (ref "R501") (pin "1") (pinfunction "1_1") (pintype "passive"))
    )
    (net (code "38") (name "Net-(D504-K)") (class "Default")
      (node (ref "C500") (pin "2") (pinfunction "2_2") (pintype "passive"))
      (node (ref "D501") (pin "3") (pinfunction "3_3") (pintype "passive"))
      (node (ref "D504") (pin "3") (pinfunction "K_3") (pintype "passive"))
      (node (ref "R500") (pin "2") (pinfunction "2_2") (pintype "passive"))
      (node (ref "U602") (pin "14") (pinfunction "PA0_14") (pintype "passive"))
    )
    (net (code "39") (name "Net-(D600-A)") (class "Default")
      (node (ref "C609") (pin "2") (pinfunction "2_2") (pintype "passive"))
      (node (ref "C630") (pin "2") (pinfunction "2_2") (pintype "passive"))
      (node (ref "D600") (pin "2") (pinfunction "A_2") (pintype "passive"))
      (node (ref "D604") (pin "2") (pinfunction "A_2") (pintype "passive"))
      (node (ref "J604") (pin "3") (pinfunction "3_3") (pintype "passive"))
      (node (ref "Q500") (pin "3") (pinfunction "3_3") (pintype "passive"))
      (node (ref "R501") (pin "2") (pinfunction "2_2") (pintype "passive"))
      (node (ref "TP22") (pin "1") (pinfunction "1_1") (pintype "passive"))
    )
    (net (code "40") (name "Net-(D601-K)") (class "Default")
      (node (ref "D601") (pin "1") (pinfunction "K_1") (pintype "passive"))
      (node (ref "R659") (pin "1") (pinfunction "1_1") (pintype "passive"))
    )
    (net (code "41") (name "Net-(D602-Pad1)") (class "Default")
      (node (ref "D602") (pin "1") (pinfunction "1_1") (pintype "passive"))
      (node (ref "D602") (pin "2") (pinfunction "2_2") (pintype "passive"))
      (node (ref "J604") (pin "1") (pinfunction "1_1") (pintype "passive"))
      (node (ref "TP20") (pin "1") (pinfunction "1_1") (pintype "passive"))
    )
    (net (code "42") (name "Net-(D604-K)") (class "Default")
      (node (ref "D604") (pin "1") (pinfunction "K_1") (pintype "passive"))
      (node (ref "T601") (pin "4") (pinfunction "4_4") (pintype "passive"))
    )
    (net (code "43") (name "Net-(D605-A)") (class "Default")
      (node (ref "C694") (pin "1") (pinfunction "1_1") (pintype "passive"))
      (node (ref "D605") (pin "2") (pinfunction "A_2") (pintype "passive"))
      (node (ref "J604") (pin "12") (pinfunction "12_12") (pintype "passive"))
      (node (ref "LB602") (pin "1") (pinfunction "1_1") (pintype "passive"))
      (node (ref "TP30") (pin "1") (pinfunction "1_1") (pintype "passive"))
    )
    (net (code "44") (name "Net-(D614-K)") (class "Default")
      (node (ref "D614") (pin "1") (pinfunction "K_1") (pintype "passive"))
      (node (ref "U602") (pin "36") (pinfunction "PB15_36") (pintype "passive"))
    )
    (net (code "45") (name "Net-(D615-K)") (class "Default")
      (node (ref "D615") (pin "1") (pinfunction "K_1") (pintype "passive"))
      (node (ref "R720") (pin "1") (pinfunction "1_1") (pintype "passive"))
      (node (ref "U610") (pin "1") (pinfunction "1_1") (pintype "passive"))
    )
    (net (code "46") (name "Net-(D617-K)") (class "Default")
      (node (ref "C673") (pin "2") (pinfunction "2_2") (pintype "passive"))
      (node (ref "C674") (pin "2") (pinfunction "2_2") (pintype "passive"))
      (node (ref "D617") (pin "1") (pinfunction "K_1") (pintype "passive"))
      (node (ref "Q604") (pin "3") (pinfunction "3_3") (pintype "passive"))
      (node (ref "R803") (pin "2") (pinfunction "2_2") (pintype "passive"))
      (node (ref "TP33") (pin "1") (pinfunction "1_1") (pintype "passive"))
    )
    (net (code "47") (name "Net-(D621-K)") (class "Default")
      (node (ref "C695") (pin "1") (pinfunction "1_1") (pintype "passive"))
      (node (ref "D621") (pin "1") (pinfunction "K_1") (pintype "passive"))
      (node (ref "J604") (pin "11") (pinfunction "11_11") (pintype "passive"))
      (node (ref "LB603") (pin "1") (pinfunction "1_1") (pintype "passive"))
      (node (ref "TP29") (pin "1") (pinfunction "1_1") (pintype "passive"))
    )
    (net (code "48") (name "Net-(D622-A)") (class "Default")
      (node (ref "C501") (pin "1") (pinfunction "1_1") (pintype "passive"))
      (node (ref "C667") (pin "2") (pinfunction "2_2") (pintype "passive"))
      (node (ref "D612") (pin "2") (pinfunction "2_2") (pintype "passive"))
      (node (ref "D613") (pin "2") (pinfunction "2_2") (pintype "passive"))
      (node (ref "D622") (pin "1") (pinfunction "A_1") (pintype "passive"))
      (node (ref "Q500") (pin "2") (pinfunction "2_2") (pintype "passive"))
      (node (ref "R836") (pin "2") (pinfunction "2_2") (pintype "passive"))
      (node (ref "TP32") (pin "1") (pinfunction "1_1") (pintype "passive"))
      (node (ref "U607") (pin "6") (pinfunction "VDD_6") (pintype "passive"))
    )
    (net (code "49") (name "Net-(J600-Pad1)") (class "Default")
      (node (ref "J600") (pin "1") (pinfunction "1_1") (pintype "passive"))
      (node (ref "R666") (pin "1") (pinfunction "1_1") (pintype "passive"))
      (node (ref "TP11") (pin "1") (pinfunction "1_1") (pintype "passive"))
    )
    (net (code "50") (name "Net-(J600-Pad3)") (class "Default")
      (node (ref "J600") (pin "3") (pinfunction "3_3") (pintype "passive"))
      (node (ref "R665") (pin "2") (pinfunction "2_2") (pintype "passive"))
      (node (ref "TP13") (pin "1") (pinfunction "1_1") (pintype "passive"))
    )
    (net (code "51") (name "Net-(J600-Pad8)") (class "Default")
      (node (ref "J600") (pin "8") (pinfunction "8_8") (pintype "passive"))
      (node (ref "R839") (pin "1") (pinfunction "1_1") (pintype "passive"))
      (node (ref "R840") (pin "1") (pinfunction "1_1") (pintype "passive"))
      (node (ref "TP36") (pin "1") (pinfunction "1_1") (pintype "passive"))
    )
    (net (code "52") (name "Net-(J600-Pad10)") (class "Default")
      (node (ref "J600") (pin "10") (pinfunction "10_10") (pintype "passive"))
      (node (ref "R619") (pin "2") (pinfunction "2_2") (pintype "passive"))
      (node (ref "TP17") (pin "1") (pinfunction "1_1") (pintype "passive"))
    )
    (net (code "53") (name "Net-(J600-Pad11)") (class "Default")
      (node (ref "J600") (pin "11") (pinfunction "11_11") (pintype "passive"))
      (node (ref "R620") (pin "2") (pinfunction "2_2") (pintype "passive"))
      (node (ref "TP18") (pin "1") (pinfunction "1_1") (pintype "passive"))
    )
    (net (code "54") (name "Net-(J600-Pad13)") (class "Default")
      (node (ref "J600") (pin "13") (pinfunction "13_13") (pintype "passive"))
      (node (ref "R609") (pin "2") (pinfunction "2_2") (pintype "passive"))
      (node (ref "TP19") (pin "1") (pinfunction "1_1") (pintype "passive"))
    )
    (net (code "55") (name "Net-(J603-Pad1)") (class "Default")
      (node (ref "J603") (pin "1") (pinfunction "1_1") (pintype "passive"))
      (node (ref "T600") (pin "3") (pinfunction "3_3") (pintype "passive"))
      (node (ref "TP1") (pin "1") (pinfunction "1_1") (pintype "passive"))
    )
    (net (code "56") (name "Net-(J603-Pad2)") (class "Default")
      (node (ref "J603") (pin "2") (pinfunction "2_2") (pintype "passive"))
      (node (ref "T600") (pin "4") (pinfunction "4_4") (pintype "passive"))
      (node (ref "TP2") (pin "1") (pinfunction "1_1") (pintype "passive"))
    )
    (net (code "57") (name "Net-(J603-Pad6)") (class "Default")
      (node (ref "J603") (pin "6") (pinfunction "6_6") (pintype "passive"))
      (node (ref "T600") (pin "5") (pinfunction "5_5") (pintype "passive"))
      (node (ref "TP3") (pin "1") (pinfunction "1_1") (pintype "passive"))
    )
    (net (code "58") (name "Net-(J603-Pad7)") (class "Default")
      (node (ref "J603") (pin "7") (pinfunction "7_7") (pintype "passive"))
      (node (ref "T600") (pin "6") (pinfunction "6_6") (pintype "passive"))
      (node (ref "TP4") (pin "1") (pinfunction "1_1") (pintype "passive"))
    )
    (net (code "59") (name "Net-(J603-Pad8)") (class "Default")
      (node (ref "J603") (pin "8") (pinfunction "8_8") (pintype "passive"))
      (node (ref "R720") (pin "2") (pinfunction "2_2") (pintype "passive"))
      (node (ref "TP6") (pin "1") (pinfunction "1_1") (pintype "passive"))
    )
    (net (code "60") (name "Net-(J603-Pad9)") (class "Default")
      (node (ref "J603") (pin "9") (pinfunction "9_9") (pintype "passive"))
      (node (ref "R721") (pin "2") (pinfunction "2_2") (pintype "passive"))
      (node (ref "TP9") (pin "1") (pinfunction "1_1") (pintype "passive"))
    )
    (net (code "61") (name "Net-(J603-Pad10)") (class "Default")
      (node (ref "J603") (pin "10") (pinfunction "10_10") (pintype "passive"))
      (node (ref "R670") (pin "2") (pinfunction "2_2") (pintype "passive"))
      (node (ref "TP7") (pin "1") (pinfunction "1_1") (pintype "passive"))
      (node (ref "U612") (pin "4") (pinfunction "4_4") (pintype "passive"))
    )
    (net (code "62") (name "Net-(J603-Pad11)") (class "Default")
      (node (ref "J603") (pin "11") (pinfunction "11_11") (pintype "passive"))
      (node (ref "Q605") (pin "3") (pinfunction "3_3") (pintype "passive"))
      (node (ref "R670") (pin "1") (pinfunction "1_1") (pintype "passive"))
      (node (ref "TP8") (pin "1") (pinfunction "1_1") (pintype "passive"))
    )
    (net (code "63") (name "Net-(J603-Pad12)") (class "Default")
      (node (ref "J603") (pin "12") (pinfunction "12_12") (pintype "passive"))
      (node (ref "TP5") (pin "1") (pinfunction "1_1") (pintype "passive"))
      (node (ref "U619") (pin "4") (pinfunction "4_4") (pintype "passive"))
    )
    (net (code "64") (name "Net-(J603-Pad13)") (class "Default")
      (node (ref "J603") (pin "13") (pinfunction "13_13") (pintype "passive"))
      (node (ref "R716") (pin "2") (pinfunction "2_2") (pintype "passive"))
      (node (ref "TP31") (pin "1") (pinfunction "1_1") (pintype "passive"))
    )
    (net (code "65") (name "Net-(J604-Pad4)") (class "Default")
      (node (ref "J604") (pin "4") (pinfunction "4_4") (pintype "passive"))
      (node (ref "R618") (pin "2") (pinfunction "2_2") (pintype "passive"))
      (node (ref "TP23") (pin "1") (pinfunction "1_1") (pintype "passive"))
    )
    (net (code "66") (name "Net-(J604-Pad6)") (class "Default")
      (node (ref "J604") (pin "6") (pinfunction "6_6") (pintype "passive"))
      (node (ref "R503") (pin "2") (pinfunction "2_2") (pintype "passive"))
      (node (ref "R695") (pin "1") (pinfunction "1_1") (pintype "passive"))
      (node (ref "TP25") (pin "1") (pinfunction "1_1") (pintype "passive"))
    )
    (net (code "67") (name "Net-(J604-Pad7)") (class "Default")
      (node (ref "J604") (pin "7") (pinfunction "7_7") (pintype "passive"))
      (node (ref "R649") (pin "2") (pinfunction "2_2") (pintype "passive"))
      (node (ref "R690") (pin "1") (pinfunction "1_1") (pintype "passive"))
      (node (ref "TP26") (pin "1") (pinfunction "1_1") (pintype "passive"))
    )
    (net (code "68") (name "Net-(J604-Pad8)") (class "Default")
      (node (ref "J604") (pin "8") (pinfunction "8_8") (pintype "passive"))
      (node (ref "R648") (pin "2") (pinfunction "2_2") (pintype "passive"))
      (node (ref "R691") (pin "1") (pinfunction "1_1") (pintype "passive"))
      (node (ref "TP27") (pin "1") (pinfunction "1_1") (pintype "passive"))
    )
    (net (code "69") (name "Net-(LB602-Pad2)") (class "Default")
      (node (ref "LB602") (pin "2") (pinfunction "2_2") (pintype "passive"))
      (node (ref "T602") (pin "2") (pinfunction "2_2") (pintype "passive"))
    )
    (net (code "70") (name "Net-(LB603-Pad2)") (class "Default")
      (node (ref "LB603") (pin "2") (pinfunction "2_2") (pintype "passive"))
      (node (ref "T602") (pin "3") (pinfunction "3_3") (pintype "passive"))
    )
    (net (code "71") (name "Net-(Q501-Pad1)") (class "Default")
      (node (ref "Q501") (pin "1") (pinfunction "1_1") (pintype "passive"))
      (node (ref "R504") (pin "1") (pinfunction "1_1") (pintype "passive"))
      (node (ref "U613") (pin "3") (pinfunction "3_3") (pintype "passive"))
    )
    (net (code "72") (name "Net-(Q603-Pad1)") (class "Default")
      (node (ref "Q603") (pin "1") (pinfunction "1_1") (pintype "passive"))
      (node (ref "R669") (pin "2") (pinfunction "2_2") (pintype "passive"))
      (node (ref "U610") (pin "3") (pinfunction "3_3") (pintype "passive"))
    )
    (net (code "73") (name "Net-(Q605-Pad1)") (class "Default")
      (node (ref "Q605") (pin "1") (pinfunction "1_1") (pintype "passive"))
      (node (ref "R813") (pin "2") (pinfunction "2_2") (pintype "passive"))
      (node (ref "U612") (pin "3") (pinfunction "3_3") (pintype "passive"))
    )
    (net (code "74") (name "Net-(R601-Pad1)") (class "Default")
      (node (ref "R601") (pin "1") (pinfunction "1_1") (pintype "passive"))
      (node (ref "R617") (pin "1") (pinfunction "1_1") (pintype "passive"))
      (node (ref "R641") (pin "1") (pinfunction "1_1") (pintype "passive"))
      (node (ref "R644") (pin "2") (pinfunction "2_2") (pintype "passive"))
      (node (ref "R689") (pin "1") (pinfunction "1_1") (pintype "passive"))
      (node (ref "R711") (pin "1") (pinfunction "1_1") (pintype "passive"))
    )
    (net (code "75") (name "Net-(R608-Pad1)") (class "Default")
      (node (ref "R608") (pin "1") (pinfunction "1_1") (pintype "passive"))
      (node (ref "R617") (pin "2") (pinfunction "2_2") (pintype "passive"))
    )
    (net (code "76") (name "Net-(R608-Pad2)") (class "Default")
      (node (ref "R608") (pin "2") (pinfunction "2_2") (pintype "passive"))
      (node (ref "R609") (pin "1") (pinfunction "1_1") (pintype "passive"))
    )
    (net (code "77") (name "Net-(R610-Pad1)") (class "Default")
      (node (ref "R610") (pin "1") (pinfunction "1_1") (pintype "passive"))
      (node (ref "R611") (pin "1") (pinfunction "1_1") (pintype "passive"))
    )
    (net (code "78") (name "Net-(R611-Pad2)") (class "Default")
      (node (ref "R611") (pin "2") (pinfunction "2_2") (pintype "passive"))
      (node (ref "R618") (pin "1") (pinfunction "1_1") (pintype "passive"))
    )
    (net (code "79") (name "Net-(R621-Pad1)") (class "Default")
      (node (ref "R621") (pin "1") (pinfunction "1_1") (pintype "passive"))
      (node (ref "R810") (pin "1") (pinfunction "1_1") (pintype "passive"))
    )
    (net (code "80") (name "Net-(R651-Pad2)") (class "Default")
      (node (ref "R651") (pin "2") (pinfunction "2_2") (pintype "passive"))
      (node (ref "T600") (pin "1") (pinfunction "1_1") (pintype "passive"))
    )
    (net (code "81") (name "Net-(R675-Pad2)") (class "Default")
      (node (ref "R675") (pin "2") (pinfunction "2_2") (pintype "passive"))
      (node (ref "R808") (pin "2") (pinfunction "2_2") (pintype "passive"))
    )
    (net (code "82") (name "Net-(R693-Pad2)") (class "Default")
      (node (ref "R693") (pin "2") (pinfunction "2_2") (pintype "passive"))
      (node (ref "U619") (pin "1") (pinfunction "1_1") (pintype "passive"))
    )
    (net (code "83") (name "Net-(R716-Pad1)") (class "Default")
      (node (ref "R716") (pin "1") (pinfunction "1_1") (pintype "passive"))
      (node (ref "U613") (pin "1") (pinfunction "1_1") (pintype "passive"))
    )
    (net (code "84") (name "Net-(R717-Pad2)") (class "Default")
      (node (ref "R717") (pin "2") (pinfunction "2_2") (pintype "passive"))
      (node (ref "U612") (pin "1") (pinfunction "1_1") (pintype "passive"))
    )
    (net (code "85") (name "Net-(R721-Pad1)") (class "Default")
      (node (ref "R721") (pin "1") (pinfunction "1_1") (pintype "passive"))
      (node (ref "U611") (pin "1") (pinfunction "1_1") (pintype "passive"))
    )
    (net (code "86") (name "Net-(R802-Pad2)") (class "Default")
      (node (ref "R802") (pin "2") (pinfunction "2_2") (pintype "passive"))
      (node (ref "R807") (pin "2") (pinfunction "2_2") (pintype "passive"))
    )
    (net (code "87") (name "Net-(R809-Pad1)") (class "Default")
      (node (ref "R809") (pin "1") (pinfunction "1_1") (pintype "passive"))
      (node (ref "R810") (pin "2") (pinfunction "2_2") (pintype "passive"))
    )
    (net (code "88") (name "Net-(U601-A)") (class "Default")
      (node (ref "C626") (pin "1") (pinfunction "1_1") (pintype "passive"))
      (node (ref "R805") (pin "2") (pinfunction "2_2") (pintype "passive"))
      (node (ref "R806") (pin "1") (pinfunction "1_1") (pintype "passive"))
      (node (ref "U601") (pin "2") (pinfunction "A_2") (pintype "passive"))
    )
    (net (code "89") (name "Net-(U601-K)") (class "Default")
      (node (ref "C626") (pin "2") (pinfunction "2_2") (pintype "passive"))
      (node (ref "Q604") (pin "1") (pinfunction "1_1") (pintype "passive"))
      (node (ref "R803") (pin "1") (pinfunction "1_1") (pintype "passive"))
      (node (ref "U601") (pin "1") (pinfunction "K_1") (pintype "passive"))
    )
    (net (code "90") (name "Net-(U602-BOOT0)") (class "Default")
      (node (ref "R837") (pin "1") (pinfunction "1_1") (pintype "passive"))
      (node (ref "U602") (pin "60") (pinfunction "BOOT0_60") (pintype "passive"))
    )
    (net (code "91") (name "Net-(U602-NRST)") (class "Default")
      (node (ref "C820") (pin "1") (pinfunction "1_1") (pintype "passive"))
      (node (ref "R838") (pin "1") (pinfunction "1_1") (pintype "passive"))
      (node (ref "U602") (pin "7") (pinfunction "NRST_7") (pintype "passive"))
    )
    (net (code "92") (name "Net-(U602-PA1)") (class "Default")
      (node (ref "C503") (pin "2") (pinfunction "2_2") (pintype "passive"))
      (node (ref "D607") (pin "3") (pinfunction "3_3") (pintype "passive"))
      (node (ref "R506") (pin "1") (pinfunction "1_1") (pintype "passive"))
      (node (ref "U602") (pin "15") (pinfunction "PA1_15") (pintype "passive"))
    )
    (net (code "93") (name "Net-(U602-PA2)") (class "Default")
      (node (ref "C645") (pin "2") (pinfunction "2_2") (pintype "passive"))
      (node (ref "D609") (pin "3") (pinfunction "3_3") (pintype "passive"))
      (node (ref "R621") (pin "2") (pinfunction "2_2") (pintype "passive"))
      (node (ref "R811") (pin "2") (pinfunction "2_2") (pintype "passive"))
      (node (ref "U602") (pin "16") (pinfunction "PA2_16") (pintype "passive"))
    )
    (net (code "94") (name "Net-(U602-PA4)") (class "Default")
      (node (ref "C646") (pin "2") (pinfunction "2_2") (pintype "passive"))
      (node (ref "D608") (pin "3") (pinfunction "3_3") (pintype "passive"))
      (node (ref "R506") (pin "2") (pinfunction "2_2") (pintype "passive"))
      (node (ref "R610") (pin "2") (pinfunction "2_2") (pintype "passive"))
      (node (ref "R706") (pin "2") (pinfunction "2_2") (pintype "passive"))
      (node (ref "U602") (pin "20") (pinfunction "PA4_20") (pintype "passive"))
      (node (ref "U602") (pin "26") (pinfunction "PB0_26") (pintype "passive"))
    )
    (net (code "95") (name "Net-(U602-PA5)") (class "Default")
      (node (ref "C644") (pin "1") (pinfunction "1_1") (pintype "passive"))
      (node (ref "R705") (pin "1") (pinfunction "1_1") (pintype "passive"))
      (node (ref "U602") (pin "21") (pinfunction "PA5_21") (pintype "passive"))
      (node (ref "U602") (pin "23") (pinfunction "PA7_23") (pintype "passive"))
    )
    (net (code "96") (name "Net-(U602-PA6)") (class "Default")
      (node (ref "C648") (pin "2") (pinfunction "2_2") (pintype "passive"))
      (node (ref "D619") (pin "3") (pinfunction "3_3") (pintype "passive"))
      (node (ref "R690") (pin "2") (pinfunction "2_2") (pintype "passive"))
      (node (ref "U602") (pin "22") (pinfunction "PA6_22") (pintype "passive"))
    )
    (net (code "97") (name "Net-(U602-PA8)") (class "Default")
      (node (ref "R600") (pin "2") (pinfunction "2_2") (pintype "passive"))
      (node (ref "U602") (pin "41") (pinfunction "PA8_41") (pintype "passive"))
      (node (ref "U618") (pin "5") (pinfunction "2B_5") (pintype "passive"))
    )
    (net (code "98") (name "Net-(U602-PA9)") (class "Default")
      (node (ref "R631") (pin "2") (pinfunction "2_2") (pintype "passive"))
      (node (ref "U602") (pin "42") (pinfunction "PA9_42") (pintype "passive"))
      (node (ref "U618") (pin "2") (pinfunction "1B_2") (pintype "passive"))
    )
    (net (code "99") (name "Net-(U602-PA10)") (class "Default")
      (node (ref "R821") (pin "1") (pinfunction "1_1") (pintype "passive"))
      (node (ref "U602") (pin "43") (pinfunction "PA10_43") (pintype "passive"))
      (node (ref "U618") (pin "10") (pinfunction "3B_10") (pintype "passive"))
    )
    (net (code "100") (name "Net-(U602-PA11)") (class "Default")
      (node (ref "R822") (pin "2") (pinfunction "2_2") (pintype "passive"))
      (node (ref "U602") (pin "44") (pinfunction "PA11_44") (pintype "passive"))
      (node (ref "U618") (pin "13") (pinfunction "4B_13") (pintype "passive"))
    )
    (net (code "101") (name "Net-(U602-PA13)") (class "Default")
      (node (ref "J601") (pin "6") (pinfunction "6_6") (pintype "passive"))
      (node (ref "R842") (pin "1") (pinfunction "1_1") (pintype "passive"))
      (node (ref "U602") (pin "46") (pinfunction "PA13_46") (pintype "passive"))
    )
    (net (code "102") (name "Net-(U602-PA14)") (class "Default")
      (node (ref "J601") (pin "10") (pinfunction "10_10") (pintype "passive"))
      (node (ref "U602") (pin "49") (pinfunction "PA14_49") (pintype "passive"))
    )
    (net (code "103") (name "Net-(U602-PA15)") (class "Default")
      (node (ref "J601") (pin "7") (pinfunction "7_7") (pintype "passive"))
      (node (ref "R841") (pin "2") (pinfunction "2_2") (pintype "passive"))
      (node (ref "U602") (pin "50") (pinfunction "PA15_50") (pintype "passive"))
    )
    (net (code "104") (name "Net-(U602-PB1)") (class "Default")
      (node (ref "C618") (pin "2") (pinfunction "2_2") (pintype "passive"))
      (node (ref "R677") (pin "1") (pinfunction "1_1") (pintype "passive"))
      (node (ref "R711") (pin "2") (pinfunction "2_2") (pintype "passive"))
      (node (ref "U602") (pin "27") (pinfunction "PB1_27") (pintype "passive"))
    )
    (net (code "105") (name "Net-(U602-PB2)") (class "Default")
      (node (ref "C689") (pin "2") (pinfunction "2_2") (pintype "passive"))
      (node (ref "R604") (pin "1") (pinfunction "1_1") (pintype "passive"))
      (node (ref "U602") (pin "28") (pinfunction "PB2_28") (pintype "passive"))
    )
    (net (code "106") (name "Net-(U602-PB3)") (class "Default")
      (node (ref "J601") (pin "9") (pinfunction "9_9") (pintype "passive"))
      (node (ref "R627") (pin "2") (pinfunction "2_2") (pintype "passive"))
      (node (ref "U602") (pin "55") (pinfunction "PB3_55") (pintype "passive"))
    )
    (net (code "107") (name "Net-(U602-PB4)") (class "Default")
      (node (ref "C614") (pin "1") (pinfunction "1_1") (pintype "passive"))
      (node (ref "J601") (pin "5") (pinfunction "5_5") (pintype "passive"))
      (node (ref "R696") (pin "1") (pinfunction "1_1") (pintype "passive"))
      (node (ref "U602") (pin "56") (pinfunction "PB4_56") (pintype "passive"))
    )
    (net (code "108") (name "Net-(U602-PB5)") (class "Default")
      (node (ref "R622") (pin "1") (pinfunction "1_1") (pintype "passive"))
      (node (ref "U602") (pin "57") (pinfunction "PB5_57") (pintype "passive"))
      (node (ref "U605") (pin "7") (pinfunction "7_7") (pintype "passive"))
    )
    (net (code "109") (name "Net-(U602-PB6)") (class "Default")
      (node (ref "R623") (pin "1") (pinfunction "1_1") (pintype "passive"))
      (node (ref "U602") (pin "58") (pinfunction "PB6_58") (pintype "passive"))
      (node (ref "U605") (pin "6") (pinfunction "6_6") (pintype "passive"))
    )
    (net (code "110") (name "Net-(U602-PB7)") (class "Default")
      (node (ref "R624") (pin "2") (pinfunction "2_2") (pintype "passive"))
      (node (ref "U602") (pin "59") (pinfunction "PB7_59") (pintype "passive"))
      (node (ref "U605") (pin "5") (pinfunction "5_5") (pintype "passive"))
    )
    (net (code "111") (name "Net-(U602-PB8)") (class "Default")
      (node (ref "C605") (pin "1") (pinfunction "1_1") (pintype "passive"))
      (node (ref "R682") (pin "1") (pinfunction "1_1") (pintype "passive"))
      (node (ref "U602") (pin "61") (pinfunction "PB8_61") (pintype "passive"))
    )
    (net (code "112") (name "Net-(U602-PB9)") (class "Default")
      (node (ref "R683") (pin "2") (pinfunction "2_2") (pintype "passive"))
      (node (ref "U602") (pin "62") (pinfunction "PB9_62") (pintype "passive"))
    )
    (net (code "113") (name "Net-(U602-PC2)") (class "Default")
      (node (ref "C616") (pin "1") (pinfunction "1_1") (pintype "passive"))
      (node (ref "D611") (pin "3") (pinfunction "3_3") (pintype "passive"))
      (node (ref "J600") (pin "5") (pinfunction "5_5") (pintype "passive"))
      (node (ref "R703") (pin "2") (pinfunction "2_2") (pintype "passive"))
      (node (ref "TP15") (pin "1") (pinfunction "1_1") (pintype "passive"))
      (node (ref "U602") (pin "10") (pinfunction "PC2_10") (pintype "passive"))
    )
    (net (code "114") (name "Net-(U602-PC3)") (class "Default")
      (node (ref "C823") (pin "2") (pinfunction "2_2") (pintype "passive"))
      (node (ref "D623") (pin "3") (pinfunction "3_3") (pintype "passive"))
      (node (ref "R839") (pin "2") (pinfunction "2_2") (pintype "passive"))
      (node (ref "U602") (pin "11") (pinfunction "PC3_11") (pintype "passive"))
    )
    (net (code "115") (name "Net-(U602-PC4)") (class "Default")
      (node (ref "C647") (pin "2") (pinfunction "2_2") (pintype "passive"))
      (node (ref "D618") (pin "3") (pinfunction "3_3") (pintype "passive"))
      (node (ref "R691") (pin "2") (pinfunction "2_2") (pintype "passive"))
      (node (ref "U602") (pin "24") (pinfunction "PC4_24") (pintype "passive"))
    )
    (net (code "116") (name "Net-(U602-PC5)") (class "Default")
      (node (ref "C604") (pin "2") (pinfunction "2_2") (pintype "passive"))
      (node (ref "D620") (pin "3") (pinfunction "3_3") (pintype "passive"))
      (node (ref "R695") (pin "2") (pinfunction "2_2") (pintype "passive"))
      (node (ref "U602") (pin "25") (pinfunction "PC5_25") (pintype "passive"))
    )
    (net (code "117") (name "Net-(U602-PC6)") (class "Default")
      (node (ref "R635") (pin "2") (pinfunction "2_2") (pintype "passive"))
      (node (ref "U602") (pin "37") (pinfunction "PC6_37") (pintype "passive"))
      (node (ref "U620") (pin "4") (pinfunction "2Y_4") (pintype "passive"))
    )
    (net (code "118") (name "Net-(U602-PC8)") (class "Default")
      (node (ref "R634") (pin "2") (pinfunction "2_2") (pintype "passive"))
      (node (ref "U602") (pin "39") (pinfunction "PC8_39") (pintype "passive"))
    )
    (net (code "119") (name "Net-(U602-PC10)") (class "Default")
      (node (ref "U602") (pin "51") (pinfunction "PC10_51") (pintype "passive"))
      (node (ref "U620") (pin "1") (pinfunction "1A_1") (pintype "passive"))
    )
    (net (code "120") (name "Net-(U602-PC11)") (class "Default")
      (node (ref "Q603") (pin "3") (pinfunction "3_3") (pintype "passive"))
      (node (ref "R812") (pin "1") (pinfunction "1_1") (pintype "passive"))
      (node (ref "U602") (pin "52") (pinfunction "PC11_52") (pintype "passive"))
    )
    (net (code "121") (name "Net-(U602-PC12)") (class "Default")
      (node (ref "C635") (pin "1") (pinfunction "1_1") (pintype "passive"))
      (node (ref "R630") (pin "1") (pinfunction "1_1") (pintype "passive"))
      (node (ref "U602") (pin "53") (pinfunction "PC12_53") (pintype "passive"))
      (node (ref "U611") (pin "3") (pinfunction "3_3") (pintype "passive"))
      (node (ref "U618") (pin "1") (pinfunction "1A_1") (pintype "passive"))
      (node (ref "U618") (pin "12") (pinfunction "4A_12") (pintype "passive"))
      (node (ref "U618") (pin "4") (pinfunction "2A_4") (pintype "passive"))
      (node (ref "U618") (pin "9") (pinfunction "3A_9") (pintype "passive"))
    )
    (net (code "122") (name "Net-(U602-PD2)") (class "Default")
      (node (ref "U602") (pin "54") (pinfunction "PD2_54") (pintype "passive"))
      (node (ref "U619") (pin "2") (pinfunction "2_2") (pintype "passive"))
    )
    (net (code "123") (name "Net-(U602-PF0)") (class "Default")
      (node (ref "C608") (pin "2") (pinfunction "2_2") (pintype "passive"))
      (node (ref "R603") (pin "2") (pinfunction "2_2") (pintype "passive"))
      (node (ref "U602") (pin "5") (pinfunction "PF0_5") (pintype "passive"))
      (node (ref "X1") (pin "1") (pinfunction "1_1") (pintype "passive"))
    )
    (net (code "124") (name "Net-(U602-PF1)") (class "Default")
      (node (ref "C653") (pin "2") (pinfunction "2_2") (pintype "passive"))
      (node (ref "R603") (pin "1") (pinfunction "1_1") (pintype "passive"))
      (node (ref "U602") (pin "6") (pinfunction "PF1_6") (pintype "passive"))
      (node (ref "X1") (pin "3") (pinfunction "3_3") (pintype "passive"))
    )
    (net (code "125") (name "Net-(U603-CANH)") (class "Default")
      (node (ref "C656") (pin "1") (pinfunction "1_1") (pintype "passive"))
      (node (ref "T602") (pin "1") (pinfunction "1_1") (pintype "passive"))
      (node (ref "U603") (pin "7") (pinfunction "CANH_7") (pintype "passive"))
    )
    (net (code "126") (name "Net-(U603-CANL)") (class "Default")
      (node (ref "C657") (pin "2") (pinfunction "2_2") (pintype "passive"))
      (node (ref "T602") (pin "4") (pinfunction "4_4") (pintype "passive"))
      (node (ref "U603") (pin "6") (pinfunction "CANL_6") (pintype "passive"))
    )
    (net (code "127") (name "Net-(U603-RXD)") (class "Default")
      (node (ref "U603") (pin "4") (pinfunction "RXD_4") (pintype "passive"))
      (node (ref "U621") (pin "7") (pinfunction "INA_7") (pintype "passive"))
    )
    (net (code "128") (name "Net-(U603-VCC)") (class "Default")
      (node (ref "C631") (pin "1") (pinfunction "1_1") (pintype "passive"))
      (node (ref "C802") (pin "2") (pinfunction "2_2") (pintype "passive"))
      (node (ref "C819") (pin "2") (pinfunction "2_2") (pintype "passive"))
      (node (ref "Q604") (pin "2") (pinfunction "2_2") (pintype "passive"))
      (node (ref "R805") (pin "1") (pinfunction "1_1") (pintype "passive"))
      (node (ref "TP34") (pin "1") (pinfunction "1_1") (pintype "passive"))
      (node (ref "U603") (pin "3") (pinfunction "VCC_3") (pintype "passive"))
      (node (ref "U621") (pin "8") (pinfunction "VDD2_8") (pintype "passive"))
    )
    (net (code "129") (name "Net-(U607-INA)") (class "Default")
      (node (ref "U607") (pin "2") (pinfunction "INA_2") (pintype "passive"))
      (node (ref "U618") (pin "3") (pinfunction "1Y_3") (pintype "passive"))
    )
    (net (code "130") (name "Net-(U607-INB)") (class "Default")
      (node (ref "U607") (pin "4") (pinfunction "INB_4") (pintype "passive"))
      (node (ref "U618") (pin "6") (pinfunction "2Y_6") (pintype "passive"))
    )
    (net (code "131") (name "Net-(U607-NA)") (class "Default")
      (node (ref "R836") (pin "1") (pinfunction "1_1") (pintype "passive"))
      (node (ref "U607") (pin "1") (pinfunction "NA/2_1") (pintype "passive"))
      (node (ref "U607") (pin "8") (pinfunction "NA_8") (pintype "passive"))
    )
    (net (code "132") (name "Net-(U607-OUTA)") (class "Default")
      (node (ref "D612") (pin "3") (pinfunction "3_3") (pintype "passive"))
      (node (ref "R651") (pin "1") (pinfunction "1_1") (pintype "passive"))
      (node (ref "U607") (pin "7") (pinfunction "OUTA_7") (pintype "passive"))
    )
    (net (code "133") (name "Net-(U607-OUTB)") (class "Default")
      (node (ref "C624") (pin "1") (pinfunction "1_1") (pintype "passive"))
      (node (ref "D613") (pin "3") (pinfunction "3_3") (pintype "passive"))
      (node (ref "U607") (pin "5") (pinfunction "OUTB_5") (pintype "passive"))
    )
    (net (code "134") (name "Net-(U615-IN+)") (class "Default")
      (node (ref "C612") (pin "2") (pinfunction "2_2") (pintype "passive"))
      (node (ref "R655") (pin "2") (pinfunction "2_2") (pintype "passive"))
      (node (ref "R677") (pin "2") (pinfunction "2_2") (pintype "passive"))
      (node (ref "R705") (pin "2") (pinfunction "2_2") (pintype "passive"))
      (node (ref "U615") (pin "1") (pinfunction "IN+_1") (pintype "passive"))
    )
    (net (code "135") (name "Net-(U615-IN-)") (class "Default")
      (node (ref "C684") (pin "1") (pinfunction "1_1") (pintype "passive"))
      (node (ref "R613") (pin "2") (pinfunction "2_2") (pintype "passive"))
      (node (ref "R654") (pin "2") (pinfunction "2_2") (pintype "passive"))
      (node (ref "R678") (pin "2") (pinfunction "2_2") (pintype "passive"))
      (node (ref "U615") (pin "3") (pinfunction "IN-_3") (pintype "passive"))
    )
    (net (code "136") (name "Net-(U615-OUT)") (class "Default")
      (node (ref "C612") (pin "1") (pinfunction "1_1") (pintype "passive"))
      (node (ref "C684") (pin "2") (pinfunction "2_2") (pintype "passive"))
      (node (ref "R612") (pin "2") (pinfunction "2_2") (pintype "passive"))
      (node (ref "R655") (pin "1") (pinfunction "1_1") (pintype "passive"))
      (node (ref "R679") (pin "2") (pinfunction "2_2") (pintype "passive"))
      (node (ref "U615") (pin "4") (pinfunction "OUT_4") (pintype "passive"))
    )
    (net (code "137") (name "Net-(U618-3Y)") (class "Default")
      (node (ref "R665") (pin "1") (pinfunction "1_1") (pintype "passive"))
      (node (ref "U618") (pin "8") (pinfunction "3Y_8") (pintype "passive"))
    )
    (net (code "138") (name "Net-(U618-4Y)") (class "Default")
      (node (ref "R666") (pin "2") (pinfunction "2_2") (pintype "passive"))
      (node (ref "U618") (pin "11") (pinfunction "4Y_11") (pintype "passive"))
    )
    (net (code "139") (name "Net-(U620-1Y)") (class "Default")
      (node (ref "R717") (pin "1") (pinfunction "1_1") (pintype "passive"))
      (node (ref "U620") (pin "6") (pinfunction "1Y_6") (pintype "passive"))
    )
    (net (code "140") (name "Net-(U620-2A)") (class "Default")
      (node (ref "C502") (pin "1") (pinfunction "1_1") (pintype "passive"))
      (node (ref "Q501") (pin "3") (pinfunction "3_3") (pintype "passive"))
      (node (ref "R505") (pin "2") (pinfunction "2_2") (pintype "passive"))
      (node (ref "U620") (pin "3") (pinfunction "2A_3") (pintype "passive"))
    )
    (net (code "141") (name "Net-(U621-OUTA)") (class "Default")
      (node (ref "R682") (pin "2") (pinfunction "2_2") (pintype "passive"))
      (node (ref "U621") (pin "2") (pinfunction "OUTA_2") (pintype "passive"))
    )
    (net (code "142") (name "Net-(U622-IN-)") (class "Default")
      (node (ref "C628") (pin "1") (pinfunction "1_1") (pintype "passive"))
      (node (ref "R713") (pin "1") (pinfunction "1_1") (pintype "passive"))
      (node (ref "U622") (pin "3") (pinfunction "IN-_3") (pintype "passive"))
    )
    (net (code "143") (name "Net-(U622-OUT)") (class "Default")
      (node (ref "C603") (pin "1") (pinfunction "1_1") (pintype "passive"))
      (node (ref "C670") (pin "1") (pinfunction "1_1") (pintype "passive"))
      (node (ref "R644") (pin "1") (pinfunction "1_1") (pintype "passive"))
      (node (ref "R701") (pin "1") (pinfunction "1_1") (pintype "passive"))
      (node (ref "U622") (pin "4") (pinfunction "OUT_4") (pintype "passive"))
    )
    (net (code "144") (name "VCC") (class "Default")
      (node (ref "C505") (pin "1") (pinfunction "1_1") (pintype "passive"))
      (node (ref "C506") (pin "1") (pinfunction "1_1") (pintype "passive"))
      (node (ref "C507") (pin "2") (pinfunction "2_2") (pintype "passive"))
      (node (ref "C613") (pin "2") (pinfunction "2_2") (pintype "passive"))
      (node (ref "C615") (pin "1") (pinfunction "1_1") (pintype "passive"))
      (node (ref "C620") (pin "2") (pinfunction "2_2") (pintype "passive"))
      (node (ref "C621") (pin "2") (pinfunction "2_2") (pintype "passive"))
      (node (ref "C636") (pin "1") (pinfunction "1_1") (pintype "passive"))
      (node (ref "C664") (pin "1") (pinfunction "1_1") (pintype "passive"))
      (node (ref "C665") (pin "2") (pinfunction "2_2") (pintype "passive"))
      (node (ref "C666") (pin "1") (pinfunction "1_1") (pintype "passive"))
      (node (ref "C675") (pin "1") (pinfunction "1_1") (pintype "passive"))
      (node (ref "C676") (pin "1") (pinfunction "1_1") (pintype "passive"))
      (node (ref "C688") (pin "2") (pinfunction "2_2") (pintype "passive"))
      (node (ref "C699") (pin "1") (pinfunction "1_1") (pintype "passive"))
      (node (ref "C700") (pin "1") (pinfunction "1_1") (pintype "passive"))
      (node (ref "C816") (pin "2") (pinfunction "2_2") (pintype "passive"))
      (node (ref "C817") (pin "2") (pinfunction "2_2") (pintype "passive"))
      (node (ref "C818") (pin "2") (pinfunction "2_2") (pintype "passive"))
      (node (ref "C821") (pin "2") (pinfunction "2_2") (pintype "passive"))
      (node (ref "C822") (pin "1") (pinfunction "1_1") (pintype "passive"))
      (node (ref "C824") (pin "2") (pinfunction "2_2") (pintype "passive"))
      (node (ref "D501") (pin "2") (pinfunction "2_2") (pintype "passive"))
      (node (ref "D603") (pin "1") (pinfunction "K_1") (pintype "passive"))
      (node (ref "D607") (pin "2") (pinfunction "2_2") (pintype "passive"))
      (node (ref "D608") (pin "2") (pinfunction "2_2") (pintype "passive"))
      (node (ref "D609") (pin "2") (pinfunction "2_2") (pintype "passive"))
      (node (ref "D611") (pin "2") (pinfunction "2_2") (pintype "passive"))
      (node (ref "D618") (pin "2") (pinfunction "2_2") (pintype "passive"))
      (node (ref "D619") (pin "2") (pinfunction "2_2") (pintype "passive"))
      (node (ref "D620") (pin "2") (pinfunction "2_2") (pintype "passive"))
      (node (ref "D623") (pin "2") (pinfunction "2_2") (pintype "passive"))
      (node (ref "J600") (pin "7") (pinfunction "7_7") (pintype "passive"))
      (node (ref "J601") (pin "8") (pinfunction "8_8") (pintype "passive"))
      (node (ref "R502") (pin "1") (pinfunction "1_1") (pintype "passive"))
      (node (ref "R503") (pin "1") (pinfunction "1_1") (pintype "passive"))
      (node (ref "R505") (pin "1") (pinfunction "1_1") (pintype "passive"))
      (node (ref "R607") (pin "2") (pinfunction "2_2") (pintype "passive"))
      (node (ref "R613") (pin "1") (pinfunction "1_1") (pintype "passive"))
      (node (ref "R622") (pin "2") (pinfunction "2_2") (pintype "passive"))
      (node (ref "R623") (pin "2") (pinfunction "2_2") (pintype "passive"))
      (node (ref "R624") (pin "1") (pinfunction "1_1") (pintype "passive"))
      (node (ref "R625") (pin "1") (pinfunction "1_1") (pintype "passive"))
      (node (ref "R626") (pin "1") (pinfunction "1_1") (pintype "passive"))
      (node (ref "R627") (pin "1") (pinfunction "1_1") (pintype "passive"))
      (node (ref "R641") (pin "2") (pinfunction "2_2") (pintype "passive"))
      (node (ref "R648") (pin "1") (pinfunction "1_1") (pintype "passive"))
      (node (ref "R649") (pin "1") (pinfunction "1_1") (pintype "passive"))
      (node (ref "R684") (pin "1") (pinfunction "1_1") (pintype "passive"))
      (node (ref "R693") (pin "1") (pinfunction "1_1") (pintype "passive"))
      (node (ref "R703") (pin "1") (pinfunction "1_1") (pintype "passive"))
      (node (ref "R812") (pin "2") (pinfunction "2_2") (pintype "passive"))
      (node (ref "R838") (pin "2") (pinfunction "2_2") (pintype "passive"))
      (node (ref "R840") (pin "2") (pinfunction "2_2") (pintype "passive"))
      (node (ref "R841") (pin "1") (pinfunction "1_1") (pintype "passive"))
      (node (ref "R842") (pin "2") (pinfunction "2_2") (pintype "passive"))
      (node (ref "TP14") (pin "1") (pinfunction "1_1") (pintype "passive"))
      (node (ref "U602") (pin "1") (pinfunction "VBAT_1") (pintype "passive"))
      (node (ref "U602") (pin "13") (pinfunction "VDD_13") (pintype "passive"))
      (node (ref "U602") (pin "19") (pinfunction "VDD_19") (pintype "passive"))
      (node (ref "U602") (pin "32") (pinfunction "VDD_32") (pintype "passive"))
      (node (ref "U602") (pin "34") (pinfunction "PB13_34") (pintype "passive"))
      (node (ref "U602") (pin "48") (pinfunction "VDD_48") (pintype "passive"))
      (node (ref "U602") (pin "64") (pinfunction "VDD_64") (pintype "passive"))
      (node (ref "U605") (pin "8") (pinfunction "8_8") (pintype "passive"))
      (node (ref "U610") (pin "4") (pinfunction "4_4") (pintype "passive"))
      (node (ref "U611") (pin "4") (pinfunction "4_4") (pintype "passive"))
      (node (ref "U613") (pin "4") (pinfunction "4_4") (pintype "passive"))
      (node (ref "U615") (pin "5") (pinfunction "VCC_5") (pintype "passive"))
      (node (ref "U618") (pin "14") (pinfunction "VCC_14") (pintype "passive"))
      (node (ref "U620") (pin "5") (pinfunction "VCC_5") (pintype "passive"))
      (node (ref "U621") (pin "1") (pinfunction "VDD_1") (pintype "passive"))
      (node (ref "U622") (pin "5") (pinfunction "VCC_5") (pintype "passive"))
    )
    (net (code "145") (name "unconnected-(1-Pad3)") (class "Default")
      (node (ref "1") (pin "3") (pinfunction "3_3") (pintype "passive"))
    )
    (net (code "146") (name "unconnected-(2-Pad3)") (class "Default")
      (node (ref "2") (pin "3") (pinfunction "3_3") (pintype "passive"))
    )
    (net (code "147") (name "unconnected-(3-Pad3)") (class "Default")
      (node (ref "3") (pin "3") (pinfunction "3_3") (pintype "passive"))
    )
    (net (code "148") (name "unconnected-(4-Pad2)") (class "Default")
      (node (ref "4") (pin "2") (pinfunction "2_2") (pintype "passive"))
    )
    (net (code "149") (name "unconnected-(5-Pad1)") (class "Default")
      (node (ref "5") (pin "1") (pinfunction "1_1") (pintype "passive"))
    )
    (net (code "150") (name "unconnected-(6-Pad3)") (class "Default")
      (node (ref "6") (pin "3") (pinfunction "3_3") (pintype "passive+no_connect"))
    )
    (net (code "151") (name "unconnected-(D502-Pad2)") (class "Default")
      (node (ref "D502") (pin "2") (pinfunction "2_2") (pintype "passive+no_connect"))
    )
    (net (code "152") (name "unconnected-(D504-Pad2)") (class "Default")
      (node (ref "D504") (pin "2") (pinfunction "2_2") (pintype "passive+no_connect"))
    )
    (net (code "153") (name "unconnected-(D622-Pad2)") (class "Default")
      (node (ref "D622") (pin "2") (pinfunction "2_2") (pintype "passive+no_connect"))
    )
    (net (code "154") (name "unconnected-(ID1-Pad1)") (class "Default")
      (node (ref "ID1") (pin "1") (pinfunction "1_1") (pintype "passive+no_connect"))
    )
    (net (code "155") (name "unconnected-(ID3-Pad1)") (class "Default")
      (node (ref "ID3") (pin "1") (pinfunction "1_1") (pintype "passive"))
    )
    (net (code "156") (name "unconnected-(ID6-Pad1)") (class "Default")
      (node (ref "ID6") (pin "1") (pinfunction "1_1") (pintype "passive"))
    )
    (net (code "157") (name "unconnected-(J600-Pad12)") (class "Default")
      (node (ref "J600") (pin "12") (pinfunction "12_12") (pintype "passive+no_connect"))
    )
    (net (code "158") (name "unconnected-(J600-Pad14)") (class "Default")
      (node (ref "J600") (pin "14") (pinfunction "14_14") (pintype "passive+no_connect"))
    )
    (net (code "159") (name "unconnected-(J601-Pad3)") (class "Default")
      (node (ref "J601") (pin "3") (pinfunction "3_3") (pintype "passive+no_connect"))
    )
    (net (code "160") (name "unconnected-(J603-Pad3)") (class "Default")
      (node (ref "J603") (pin "3") (pinfunction "3_3") (pintype "passive+no_connect"))
    )
    (net (code "161") (name "unconnected-(J603-Pad4)") (class "Default")
      (node (ref "J603") (pin "4") (pinfunction "4_4") (pintype "passive+no_connect"))
    )
    (net (code "162") (name "unconnected-(J604-Pad10)") (class "Default")
      (node (ref "J604") (pin "10") (pinfunction "10_10") (pintype "passive+no_connect"))
    )
    (net (code "163") (name "unconnected-(J604-Pad13)") (class "Default")
      (node (ref "J604") (pin "13") (pinfunction "13_13") (pintype "passive+no_connect"))
    )
    (net (code "164") (name "unconnected-(TP10-Pad1)") (class "Default")
      (node (ref "TP10") (pin "1") (pinfunction "1_1") (pintype "passive+no_connect"))
    )
    (net (code "165") (name "unconnected-(U602-PA3-Pad17)") (class "Default")
      (node (ref "U602") (pin "17") (pinfunction "PA3_17") (pintype "passive+no_connect"))
    )
    (net (code "166") (name "unconnected-(U602-PA12-Pad45)") (class "Default")
      (node (ref "U602") (pin "45") (pinfunction "PA12_45") (pintype "passive+no_connect"))
    )
    (net (code "167") (name "unconnected-(U602-PB10-Pad29)") (class "Default")
      (node (ref "U602") (pin "29") (pinfunction "PB10_29") (pintype "passive+no_connect"))
    )
    (net (code "168") (name "unconnected-(U602-PB11-Pad30)") (class "Default")
      (node (ref "U602") (pin "30") (pinfunction "PB11_30") (pintype "passive+no_connect"))
    )
    (net (code "169") (name "unconnected-(U602-PB14-Pad35)") (class "Default")
      (node (ref "U602") (pin "35") (pinfunction "PB14_35") (pintype "passive+no_connect"))
    )
    (net (code "170") (name "unconnected-(U602-PC0-Pad8)") (class "Default")
      (node (ref "U602") (pin "8") (pinfunction "PC0_8") (pintype "passive+no_connect"))
    )
    (net (code "171") (name "unconnected-(U602-PC1-Pad9)") (class "Default")
      (node (ref "U602") (pin "9") (pinfunction "PC1_9") (pintype "passive+no_connect"))
    )
    (net (code "172") (name "unconnected-(U602-PC7-Pad38)") (class "Default")
      (node (ref "U602") (pin "38") (pinfunction "PC7_38") (pintype "passive+no_connect"))
    )
    (net (code "173") (name "unconnected-(U602-PC9-Pad40)") (class "Default")
      (node (ref "U602") (pin "40") (pinfunction "PC9_40") (pintype "passive+no_connect"))
    )
    (net (code "174") (name "unconnected-(U602-PC13-Pad2)") (class "Default")
      (node (ref "U602") (pin "2") (pinfunction "PC13_2") (pintype "passive+no_connect"))
    )
    (net (code "175") (name "unconnected-(U602-PC14-Pad3)") (class "Default")
      (node (ref "U602") (pin "3") (pinfunction "PC14_3") (pintype "passive+no_connect"))
    )
    (net (code "176") (name "unconnected-(U602-PC15-Pad4)") (class "Default")
      (node (ref "U602") (pin "4") (pinfunction "PC15_4") (pintype "passive+no_connect"))
    )
    (net (code "177") (name "unconnected-(U603-VIO-Pad5)") (class "Default")
      (node (ref "U603") (pin "5") (pinfunction "VIO_5") (pintype "passive+no_connect"))
    )
  )
)
